# FPGABoard.net
KiCad netlist of a schematic drawn in Altium Designer
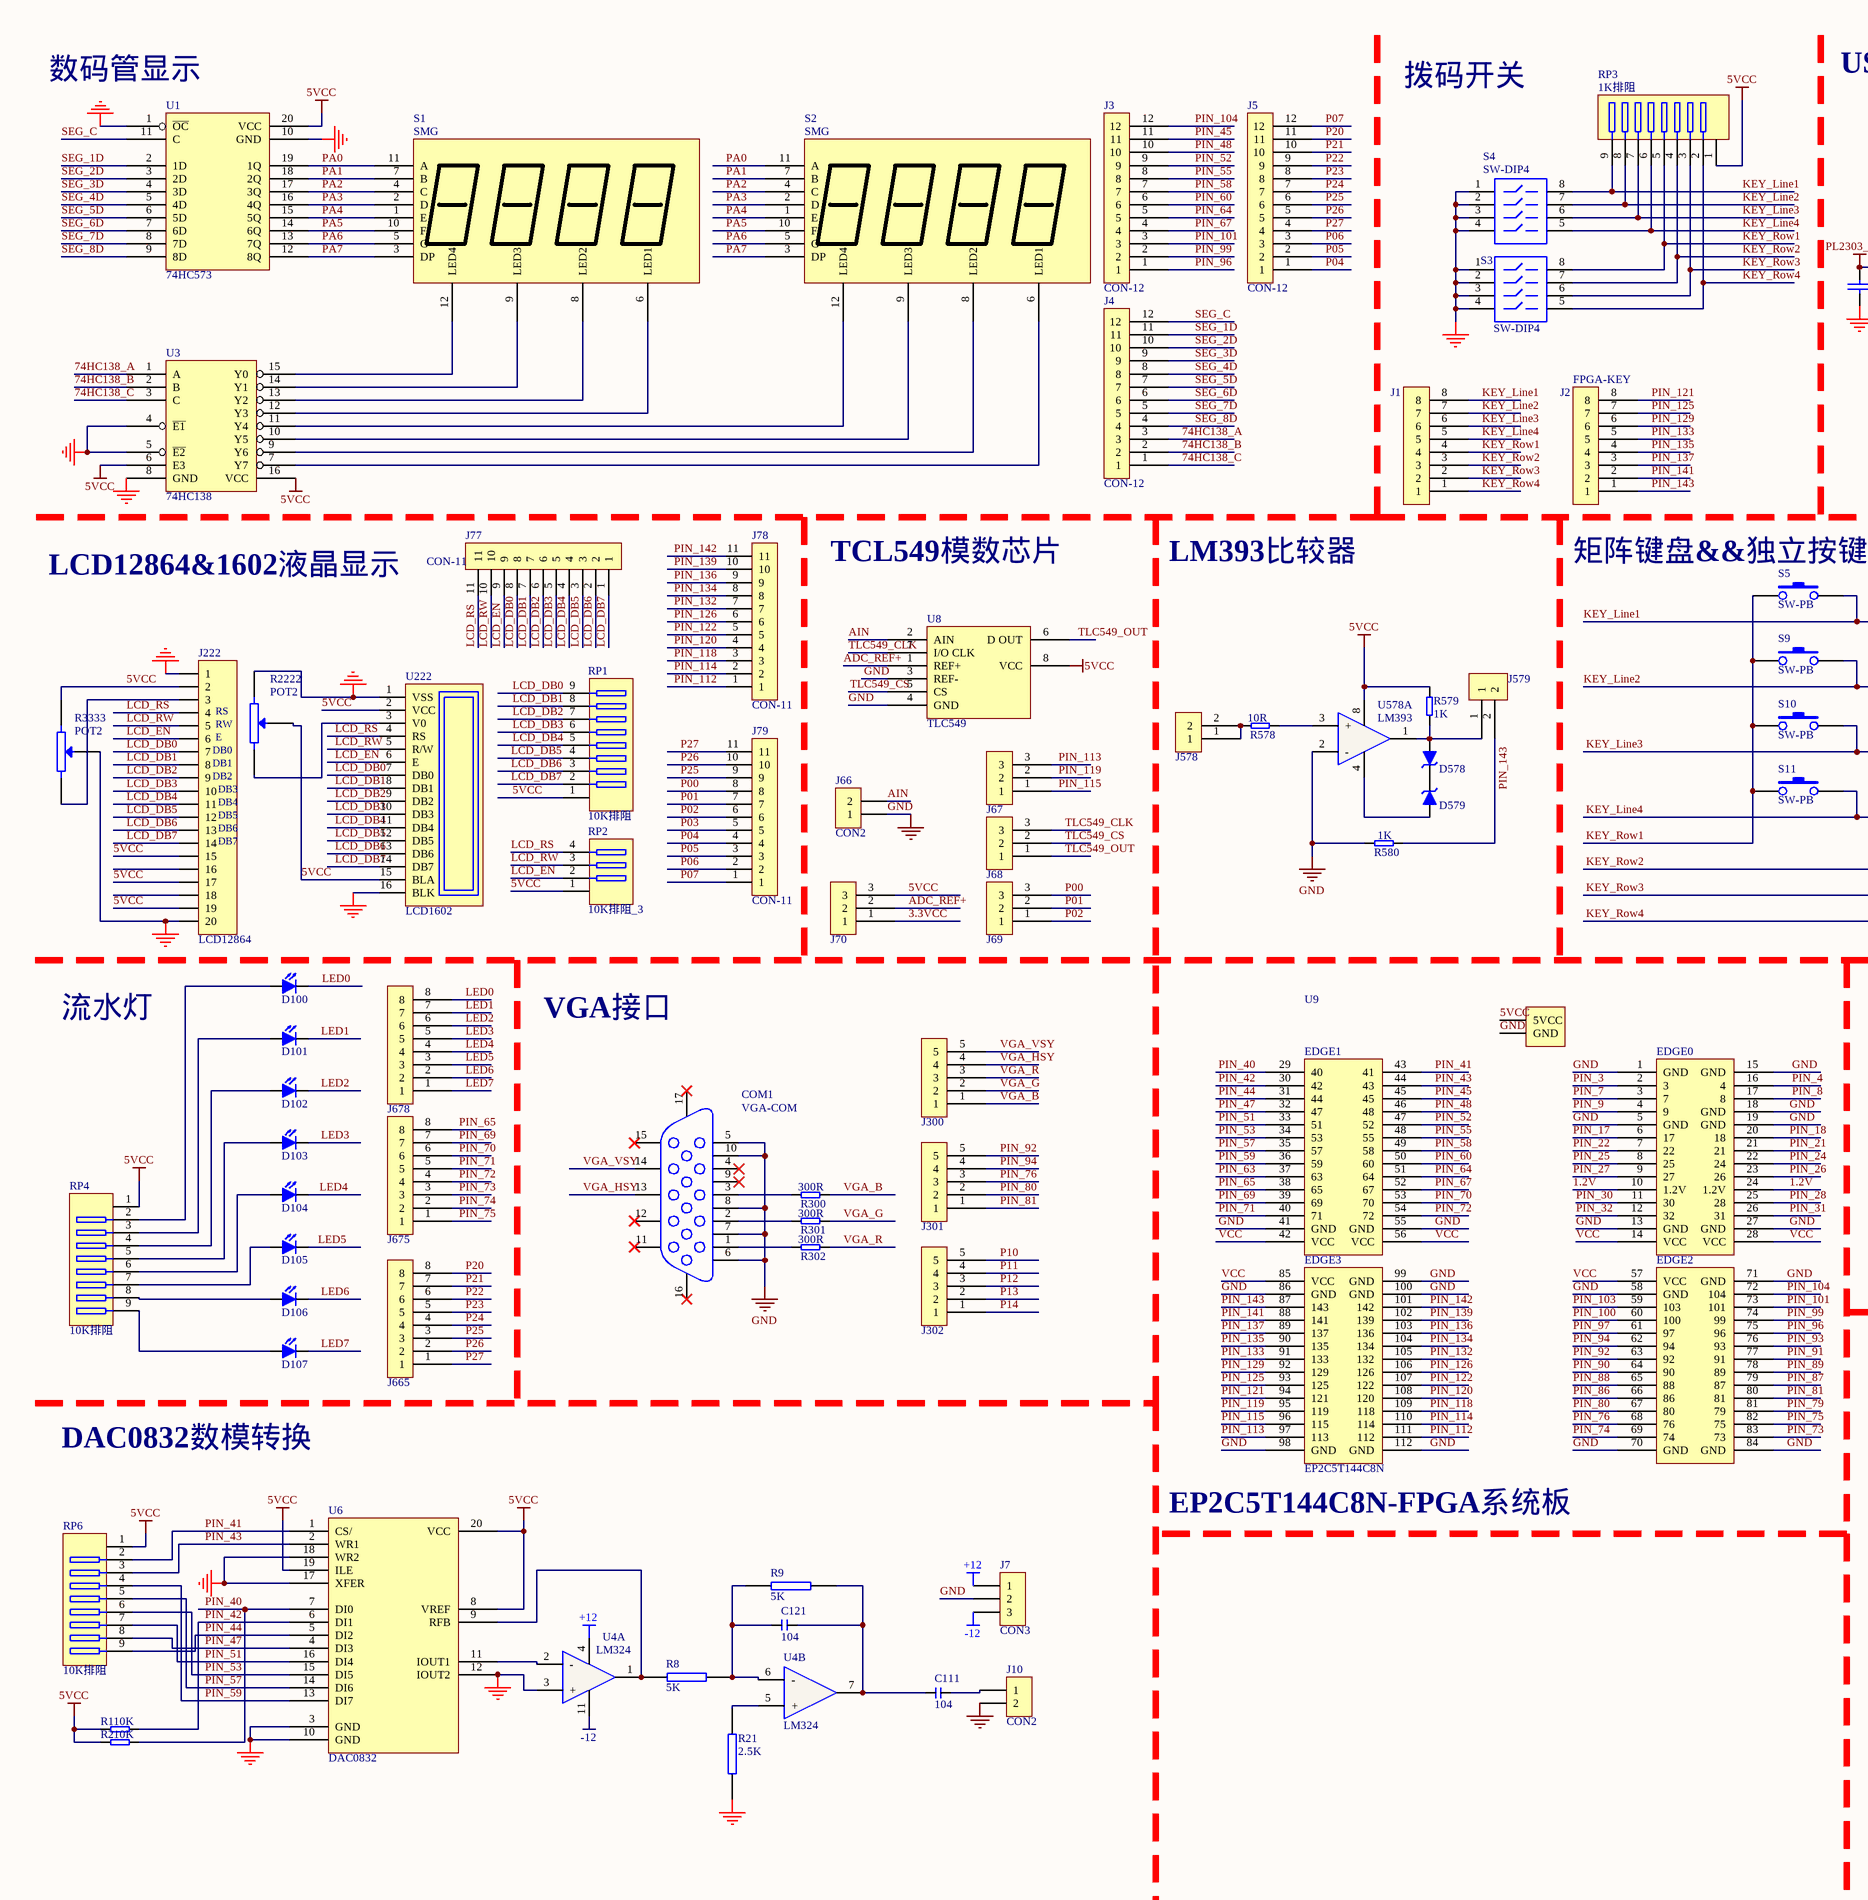
[diagram p0: FPGABoard.SchDoc, left]
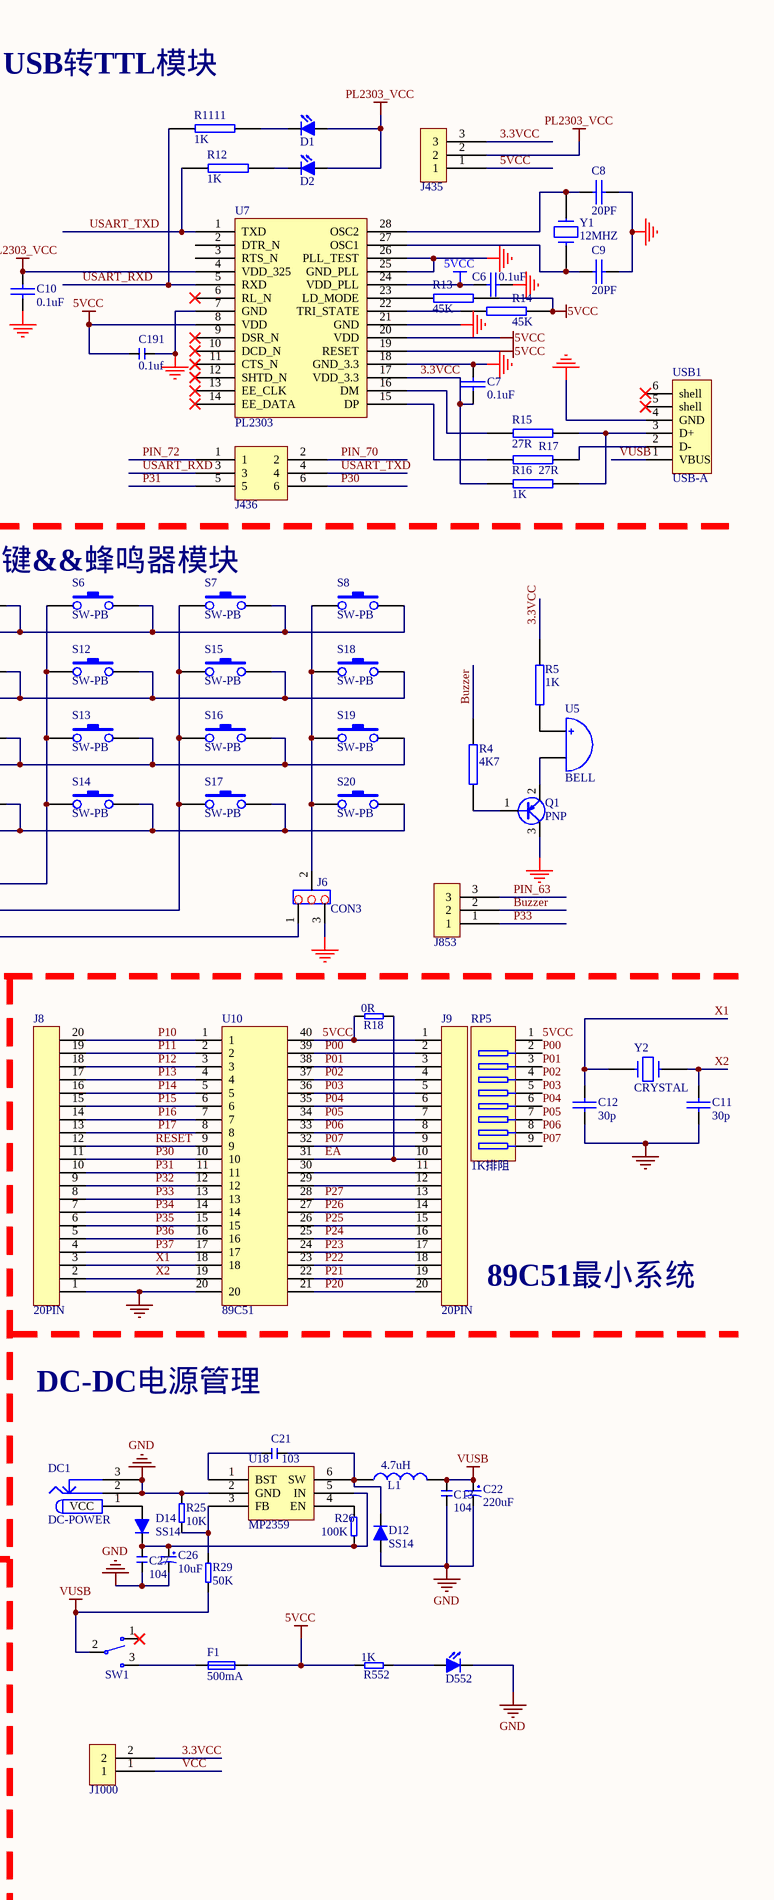
[diagram p1: FPGABoard.SchDoc, right]

(export (version "E")
  (design (tool "Eeschema 10.0.6"))
  (components
    (comp (ref "C6")
      (value "0.1uF")
      (footprint "C0805")
      (description "Capacitor")
      (libsource (lib "*") (part "CAP"))
    )
    (comp (ref "C7")
      (value "0.1uF")
      (footprint "C0805")
      (description "Capacitor")
      (libsource (lib "*") (part "CAP"))
    )
    (comp (ref "C8")
      (value "20PF")
      (footprint "C0805")
      (description "Capacitor")
      (libsource (lib "*") (part "CAP"))
    )
    (comp (ref "C9")
      (value "20PF")
      (footprint "C0805")
      (description "Capacitor")
      (libsource (lib "*") (part "CAP"))
    )
    (comp (ref "C10")
      (value "0.1uF")
      (footprint "C0805")
      (description "Capacitor")
      (libsource (lib "*") (part "CAP"))
    )
    (comp (ref "C11")
      (value "30p")
      (footprint "0805")
      (description "Capacitor")
      (libsource (lib "*") (part "CAP"))
    )
    (comp (ref "C12")
      (value "30p")
      (footprint "0805")
      (description "Capacitor")
      (libsource (lib "*") (part "CAP"))
    )
    (comp (ref "C13") (value "104") (footprint "C0805") (libsource (lib "Allcomments") (part "CAP")))
    (comp (ref "C21") (value "103") (footprint "C0805") (libsource (lib "Allcomments") (part "CAP")))
    (comp (ref "C22")
      (value "220uF")
      (footprint "CA-6.3mmx6.3mm")
      (libsource (lib "Allcomments") (part "CAP-ELEC"))
    )
    (comp (ref "C26")
      (value "10uF")
      (footprint "CA-A-3216L")
      (libsource (lib "Allcomments") (part "CAP-ELEC"))
    )
    (comp (ref "C27") (value "104") (footprint "C0805") (libsource (lib "Allcomments") (part "CAP")))
    (comp (ref "C111") (value "104") (footprint "C0805") (libsource (lib "原理图总库") (part "CAP")))
    (comp (ref "C121") (value "104") (footprint "C0805") (libsource (lib "原理图总库") (part "CAP")))
    (comp (ref "C191") (value "0.1uf") (footprint "C0805") (libsource (lib "Allcomments") (part "CAP")))
    (comp (ref "COM1") (value "VGA-COM") (footprint "VGA-15") (libsource (lib "原理图总库") (part "VGA-COM")))
    (comp (ref "D1") (value "LED") (footprint "LED0805-RED") (libsource (lib "Allcomments") (part "LED")))
    (comp (ref "D2") (value "LED") (footprint "LED0805-RED") (libsource (lib "Allcomments") (part "LED")))
    (comp (ref "D12") (value "SS14") (footprint "DO-214") (libsource (lib "Allcomments") (part "DIODE")))
    (comp (ref "D14") (value "SS14") (footprint "DO-214") (libsource (lib "Allcomments") (part "DIODE")))
    (comp (ref "D100") (value "LED") (footprint "LED0805-RED") (libsource (lib "原理图总库") (part "LED")))
    (comp (ref "D101") (value "LED") (footprint "LED0805-RED") (libsource (lib "原理图总库") (part "LED")))
    (comp (ref "D102") (value "LED") (footprint "LED0805-RED") (libsource (lib "原理图总库") (part "LED")))
    (comp (ref "D103") (value "LED") (footprint "LED0805-RED") (libsource (lib "原理图总库") (part "LED")))
    (comp (ref "D104") (value "LED") (footprint "LED0805-RED") (libsource (lib "原理图总库") (part "LED")))
    (comp (ref "D105") (value "LED") (footprint "LED0805-RED") (libsource (lib "原理图总库") (part "LED")))
    (comp (ref "D106") (value "LED") (footprint "LED0805-RED") (libsource (lib "原理图总库") (part "LED")))
    (comp (ref "D107") (value "LED") (footprint "LED0805-RED") (libsource (lib "原理图总库") (part "LED")))
    (comp (ref "D552") (value "LED") (footprint "LED0805-GREEN") (libsource (lib "原理图总库") (part "LED")))
    (comp (ref "D578")
      (value "DIODE-ZENER3")
      (footprint "D1206")
      (libsource (lib "原理图总库") (part "DIODE-ZENER3"))
    )
    (comp (ref "D579")
      (value "DIODE-ZENER3")
      (footprint "D1206")
      (libsource (lib "原理图总库") (part "DIODE-ZENER3"))
    )
    (comp (ref "DC1") (value "DC-POWER") (footprint "DC-5v") (libsource (lib "Allcomments") (part "DC")))
    (comp (ref "F1") (value "500mA") (footprint "0805") (libsource (lib "Allcomments") (part "FUSE")))
    (comp (ref "J1") (value "CON-8") (footprint "SIP8-2.54") (libsource (lib "Allcomments") (part "CON-8")))
    (comp (ref "J2")
      (value "FPGA-KEY")
      (footprint "SIP8-2.54")
      (libsource (lib "Allcomments") (part "CON-8"))
    )
    (comp (ref "J3")
      (value "CON-12")
      (footprint "SIP12-2.54")
      (libsource (lib "Allcomments") (part "CON-12"))
    )
    (comp (ref "J4")
      (value "CON-12")
      (footprint "SIP12-2.54")
      (libsource (lib "Allcomments") (part "CON-12"))
    )
    (comp (ref "J5")
      (value "CON-12")
      (footprint "SIP12-2.54")
      (libsource (lib "Allcomments") (part "CON-12"))
    )
    (comp (ref "J6") (value "CON3") (footprint "SIP3-2.54") (libsource (lib "") (part "CON3_1")))
    (comp (ref "J7")
      (value "CON3")
      (footprint "SIP3-2.54")
      (description "Connector")
      (libsource (lib "*") (part "CON3"))
    )
    (comp (ref "J8") (value "20PIN") (footprint "SIP20-2.54") (libsource (lib "") (part "20PIN_1")))
    (comp (ref "J9") (value "20PIN") (footprint "SIP20-2.54") (libsource (lib "*") (part "20PIN")))
    (comp (ref "J10")
      (value "CON2")
      (footprint "SIP2-2.54")
      (description "Connector")
      (libsource (lib "") (part "CON2_1"))
    )
    (comp (ref "J66")
      (value "CON2")
      (footprint "SIP2-2.54")
      (description "Connector")
      (libsource (lib "*") (part "CON2"))
    )
    (comp (ref "J67") (value "CON-3") (footprint "SIP3-2.54") (libsource (lib "原理图总库") (part "CON-3")))
    (comp (ref "J68") (value "CON-3") (footprint "SIP3-2.54") (libsource (lib "原理图总库") (part "CON-3")))
    (comp (ref "J69") (value "CON-3") (footprint "SIP3-2.54") (libsource (lib "原理图总库") (part "CON-3")))
    (comp (ref "J70") (value "CON-3") (footprint "SIP3-2.54") (libsource (lib "Allcomments") (part "CON-3")))
    (comp (ref "J77") (value "CON-11") (footprint "SIP11-2.54") (libsource (lib "") (part "CON-11_1")))
    (comp (ref "J78") (value "CON-11") (footprint "SIP11-2.54") (libsource (lib "原理图总库") (part "CON-11")))
    (comp (ref "J79") (value "CON-11") (footprint "SIP11-2.54") (libsource (lib "原理图总库") (part "CON-11")))
    (comp (ref "J222")
      (value "LCD12864")
      (footprint "SIP20-2.54")
      (description "20PIN")
      (libsource (lib "*") (part "LCD12864"))
    )
    (comp (ref "J300") (value "CON-5") (footprint "SIP5-2.54") (libsource (lib "原理图总库") (part "CON-5")))
    (comp (ref "J301") (value "CON-5") (footprint "SIP5-2.54") (libsource (lib "原理图总库") (part "CON-5")))
    (comp (ref "J302") (value "CON-5") (footprint "SIP5-2.54") (libsource (lib "原理图总库") (part "CON-5")))
    (comp (ref "J435") (value "CON-3") (footprint "SIP3-2.54") (libsource (lib "Allcomments") (part "CON-3")))
    (comp (ref "J436")
      (value "CON-2*3")
      (footprint "J2X3-2.54mm")
      (libsource (lib "Allcomments") (part "CON-2*3"))
    )
    (comp (ref "J578") (value "CON-2") (footprint "J1x2-2.54mm") (libsource (lib "") (part "CON-2_1")))
    (comp (ref "J579") (value "CON-2") (footprint "J1x2-2.54mm") (libsource (lib "原理图总库") (part "CON-2")))
    (comp (ref "J665") (value "CON-8") (footprint "SIP8-2.54") (libsource (lib "原理图总库") (part "CON-8")))
    (comp (ref "J675") (value "CON-8") (footprint "SIP8-2.54") (libsource (lib "原理图总库") (part "CON-8")))
    (comp (ref "J678") (value "CON-8") (footprint "SIP8-2.54") (libsource (lib "原理图总库") (part "CON-8")))
    (comp (ref "J853") (value "CON-3") (footprint "SIP3-2.54") (libsource (lib "原理图总库") (part "CON-3")))
    (comp (ref "J1000") (value "CON-2") (footprint "J1x2-2.54mm") (libsource (lib "") (part "CON-2_1")))
    (comp (ref "L1") (value "4.7uH") (footprint "L-SOP74") (libsource (lib "Allcomments") (part "INDUCTOR")))
    (comp (ref "Q1") (value "PNP") (footprint "SOT-23A") (libsource (lib "原理图总库") (part "AUDION-PNP")))
    (comp (ref "R1") (value "10K") (footprint "R-0805") (libsource (lib "Allcomments") (part "RES")))
    (comp (ref "R2") (value "10K") (footprint "R-0805") (libsource (lib "Allcomments") (part "RES")))
    (comp (ref "R4") (value "4K7") (footprint "R0805") (libsource (lib "*") (part "RES2")))
    (comp (ref "R5") (value "1K") (footprint "R0805") (libsource (lib "*") (part "RES2")))
    (comp (ref "R8") (value "5K") (footprint "R0805") (libsource (lib "*") (part "RES2")))
    (comp (ref "R9") (value "5K") (footprint "R0805") (libsource (lib "*") (part "RES2")))
    (comp (ref "R12") (value "1K") (footprint "0805") (libsource (lib "*") (part "RES2")))
    (comp (ref "R13") (value "45K") (footprint "0805") (libsource (lib "*") (part "RES2")))
    (comp (ref "R14") (value "45K") (footprint "0805") (libsource (lib "*") (part "RES2")))
    (comp (ref "R15") (value "27R") (footprint "0805") (libsource (lib "*") (part "RES2")))
    (comp (ref "R16") (value "1K") (footprint "0805") (libsource (lib "*") (part "RES2")))
    (comp (ref "R17") (value "27R") (footprint "0805") (libsource (lib "*") (part "RES2")))
    (comp (ref "R18") (value "0R") (footprint "R0805") (libsource (lib "Allcomments") (part "RES")))
    (comp (ref "R21") (value "2.5K") (footprint "R0805") (libsource (lib "*") (part "RES2")))
    (comp (ref "R25") (value "10K") (footprint "R-0805") (libsource (lib "Allcomments") (part "RES")))
    (comp (ref "R26") (value "100K") (footprint "R-0805") (libsource (lib "Allcomments") (part "RES")))
    (comp (ref "R29") (value "50K") (footprint "R-0805") (libsource (lib "Allcomments") (part "RES")))
    (comp (ref "R300") (value "300R") (footprint "R-0805") (libsource (lib "原理图总库") (part "RES")))
    (comp (ref "R301") (value "300R") (footprint "R-0805") (libsource (lib "原理图总库") (part "RES")))
    (comp (ref "R302") (value "300R") (footprint "R-0805") (libsource (lib "原理图总库") (part "RES")))
    (comp (ref "R552") (value "1K") (footprint "0805") (libsource (lib "原理图总库") (part "RES")))
    (comp (ref "R578") (value "10R") (footprint "R-0805") (libsource (lib "原理图总库") (part "RES")))
    (comp (ref "R579") (value "1K") (footprint "R-0805") (libsource (lib "原理图总库") (part "RES")))
    (comp (ref "R580") (value "1K") (footprint "R-0805") (libsource (lib "原理图总库") (part "RES")))
    (comp (ref "R1111") (value "1K") (footprint "0805") (libsource (lib "*") (part "RES2")))
    (comp (ref "R2222")
      (value "POT2")
      (footprint "VR5")
      (description "Potentiometer")
      (libsource (lib "*") (part "POT2"))
    )
    (comp (ref "R3333")
      (value "POT2")
      (footprint "VR5")
      (description "Potentiometer")
      (libsource (lib "*") (part "POT2"))
    )
    (comp (ref "RP1")
      (value "10K排阻")
      (footprint "SIP9-2.54")
      (description "330")
      (libsource (lib "") (part "10K排阻_2"))
    )
    (comp (ref "RP2")
      (value "10K排阻_3")
      (footprint "SIP4-2.54")
      (description "330")
      (libsource (lib "*") (part "10K排阻_3"))
    )
    (comp (ref "RP3")
      (value "1K排阻")
      (footprint "SIP9-2.54")
      (description "330")
      (libsource (lib "") (part "10K排阻_1"))
    )
    (comp (ref "RP4")
      (value "10K排阻")
      (footprint "SIP9-2.54")
      (description "330")
      (libsource (lib "*") (part "10K排阻"))
    )
    (comp (ref "RP5")
      (value "1K排阻")
      (footprint "SIP9-2.54")
      (description "330")
      (libsource (lib "*") (part "10K排阻"))
    )
    (comp (ref "RP6")
      (value "10K排阻")
      (footprint "SIP9-2.54")
      (description "330")
      (libsource (lib "*") (part "10K排阻"))
    )
    (comp (ref "S1") (value "SMG") (footprint "LED4_0.28_DIP12") (libsource (lib "*") (part "SMG")))
    (comp (ref "S2") (value "SMG") (footprint "LED4_0.28_DIP12") (libsource (lib "*") (part "SMG")))
    (comp (ref "S3") (value "SW-DIP4") (footprint "DIP-KEY-4") (libsource (lib "*") (part "SW-DIP4")))
    (comp (ref "S4") (value "SW-DIP4") (footprint "DIP-KEY-4") (libsource (lib "*") (part "SW-DIP4")))
    (comp (ref "S5") (value "SW-PB") (footprint "KEY") (libsource (lib "*") (part "SW-PB")))
    (comp (ref "S6") (value "SW-PB") (footprint "KEY") (libsource (lib "*") (part "SW-PB")))
    (comp (ref "S7") (value "SW-PB") (footprint "KEY") (libsource (lib "*") (part "SW-PB")))
    (comp (ref "S8") (value "SW-PB") (footprint "KEY") (libsource (lib "*") (part "SW-PB")))
    (comp (ref "S9") (value "SW-PB") (footprint "KEY") (libsource (lib "*") (part "SW-PB")))
    (comp (ref "S10") (value "SW-PB") (footprint "KEY") (libsource (lib "*") (part "SW-PB")))
    (comp (ref "S11") (value "SW-PB") (footprint "KEY") (libsource (lib "*") (part "SW-PB")))
    (comp (ref "S12") (value "SW-PB") (footprint "KEY") (libsource (lib "*") (part "SW-PB")))
    (comp (ref "S13") (value "SW-PB") (footprint "KEY") (libsource (lib "*") (part "SW-PB")))
    (comp (ref "S14") (value "SW-PB") (footprint "KEY") (libsource (lib "*") (part "SW-PB")))
    (comp (ref "S15") (value "SW-PB") (footprint "KEY") (libsource (lib "*") (part "SW-PB")))
    (comp (ref "S16") (value "SW-PB") (footprint "KEY") (libsource (lib "*") (part "SW-PB")))
    (comp (ref "S17") (value "SW-PB") (footprint "KEY") (libsource (lib "*") (part "SW-PB")))
    (comp (ref "S18") (value "SW-PB") (footprint "KEY") (libsource (lib "*") (part "SW-PB")))
    (comp (ref "S19") (value "SW-PB") (footprint "KEY") (libsource (lib "*") (part "SW-PB")))
    (comp (ref "S20") (value "SW-PB") (footprint "KEY") (libsource (lib "*") (part "SW-PB")))
    (comp (ref "SW1")
      (value "SW-SPDP")
      (footprint "SW-DPDT")
      (libsource (lib "Allcomments") (part "SW-SPDP"))
    )
    (comp (ref "U1") (value "74HC573") (footprint "SO-20W") (libsource (lib "*") (part "74HC573")))
    (comp (ref "U3") (value "74HC138") (footprint "SOP-16-NB") (libsource (lib "*") (part "74HC138")))
    (comp (ref "U4") (value "LM324") (footprint "SOP14-225-50") (libsource (lib "原理图总库") (part "LM324")))
    (comp (ref "U5")
      (value "BELL")
      (footprint "BELL")
      (description "Bell")
      (libsource (lib "*") (part "BELL"))
    )
    (comp (ref "U6") (value "DAC0832") (footprint "DIP-20N") (libsource (lib "*") (part "DAC0832")))
    (comp (ref "U7") (value "PL2303") (footprint "SSOP-SS28_N") (libsource (lib "*") (part "PL2303")))
    (comp (ref "U8") (value "TLC549") (footprint "SOP-8-NB") (libsource (lib "*") (part "TLC549")))
    (comp (ref "U9") (value "EP2C5T144C8N") (footprint "HXB") (libsource (lib "*") (part "EP2C5T144C8N")))
    (comp (ref "U10") (value "89C51") (footprint "ZIP_40") (libsource (lib "*") (part "89C51")))
    (comp (ref "U18") (value "MP2359") (footprint "SOT23-6") (libsource (lib "Allcomments") (part "MP2359")))
    (comp (ref "U222")
      (value "LCD1602")
      (footprint "SIP16-2.54")
      (description "16PIN")
      (libsource (lib "*") (part "LCD1602"))
    )
    (comp (ref "U578") (value "LM393") (footprint "SOP-8-NB") (libsource (lib "原理图总库") (part "LM393")))
    (comp (ref "USB1")
      (value "USB-A")
      (footprint "USB-HD-1X1-1")
      (libsource (lib "Allcomments") (part "USB-A"))
    )
    (comp (ref "Y1")
      (value "12MHZ")
      (footprint "XTAL")
      (description "Crystal")
      (libsource (lib "*") (part "CRYSTAL"))
    )
    (comp (ref "Y2")
      (value "CRYSTAL")
      (footprint "XTAL2")
      (description "Crystal")
      (libsource (lib "*") (part "CRYSTAL"))
    )
  )
  (nets
    (net (code "1") (name "+12") (class "Default")
      (node (ref "J7") (pin "1") (pinfunction "1_1") (pintype "passive"))
      (node (ref "U4") (pin "4") (pinfunction "4_4") (pintype "passive"))
    )
    (net (code "2") (name "-12") (class "Default")
      (node (ref "J7") (pin "3") (pinfunction "3_3") (pintype "passive"))
      (node (ref "U4") (pin "11") (pinfunction "11_11") (pintype "passive"))
    )
    (net (code "3") (name "/1.2V") (class "Default")
      (node (ref "U9") (pin "10") (pinfunction "1.2V_10") (pintype "passive"))
      (node (ref "U9") (pin "24") (pinfunction "1.2V_24") (pintype "passive"))
    )
    (net (code "4") (name "/3.3VCC") (class "Default")
      (node (ref "C7") (pin "2") (pinfunction "2_2") (pintype "passive"))
      (node (ref "J1000") (pin "2") (pinfunction "2_2") (pintype "passive"))
      (node (ref "J435") (pin "3") (pinfunction "3_3") (pintype "passive"))
      (node (ref "J70") (pin "1") (pinfunction "1_1") (pintype "passive"))
      (node (ref "R16") (pin "2") (pinfunction "2_2") (pintype "passive"))
      (node (ref "R5") (pin "2") (pinfunction "2_2") (pintype "passive"))
      (node (ref "U7") (pin "17") (pinfunction "VDD_3.3_17") (pintype "passive"))
    )
    (net (code "5") (name "/74HC138_A") (class "Default")
      (node (ref "J4") (pin "3") (pinfunction "3_3") (pintype "passive"))
      (node (ref "U3") (pin "1") (pinfunction "A_1") (pintype "passive"))
    )
    (net (code "6") (name "/74HC138_B") (class "Default")
      (node (ref "J4") (pin "2") (pinfunction "2_2") (pintype "passive"))
      (node (ref "U3") (pin "2") (pinfunction "B_2") (pintype "passive"))
    )
    (net (code "7") (name "/74HC138_C") (class "Default")
      (node (ref "J4") (pin "1") (pinfunction "1_1") (pintype "passive"))
      (node (ref "U3") (pin "3") (pinfunction "C_3") (pintype "passive"))
    )
    (net (code "8") (name "/ADC_REF+") (class "Default")
      (node (ref "J70") (pin "2") (pinfunction "2_2") (pintype "passive"))
      (node (ref "U8") (pin "1") (pinfunction "REF+_1") (pintype "passive"))
    )
    (net (code "9") (name "/AIN") (class "Default")
      (node (ref "J66") (pin "2") (pinfunction "2_2") (pintype "passive"))
      (node (ref "U8") (pin "2") (pinfunction "AIN_2") (pintype "passive"))
    )
    (net (code "10") (name "/Buzzer") (class "Default")
      (node (ref "J853") (pin "2") (pinfunction "2_2") (pintype "passive"))
      (node (ref "R4") (pin "1") (pinfunction "1_1") (pintype "passive"))
    )
    (net (code "11") (name "/EA") (class "Default")
      (node (ref "J9") (pin "10") (pinfunction "10_10") (pintype "passive"))
      (node (ref "R18") (pin "2") (pinfunction "2_2") (pintype "passive"))
      (node (ref "U10") (pin "31") (pinfunction "31_31") (pintype "passive"))
    )
    (net (code "12") (name "/KEY_Line1") (class "Default")
      (node (ref "J1") (pin "8") (pinfunction "8_8") (pintype "passive"))
      (node (ref "RP3") (pin "9") (pinfunction "9_9") (pintype "passive"))
      (node (ref "S4") (pin "8") (pinfunction "8_8") (pintype "passive"))
      (node (ref "S5") (pin "3") (pinfunction "3_3") (pintype "passive"))
      (node (ref "S6") (pin "3") (pinfunction "3_3") (pintype "passive"))
      (node (ref "S7") (pin "3") (pinfunction "3_3") (pintype "passive"))
      (node (ref "S8") (pin "3") (pinfunction "3_3") (pintype "passive"))
    )
    (net (code "13") (name "/KEY_Line2") (class "Default")
      (node (ref "J1") (pin "7") (pinfunction "7_7") (pintype "passive"))
      (node (ref "RP3") (pin "8") (pinfunction "8_8") (pintype "passive"))
      (node (ref "S12") (pin "3") (pinfunction "3_3") (pintype "passive"))
      (node (ref "S15") (pin "3") (pinfunction "3_3") (pintype "passive"))
      (node (ref "S18") (pin "3") (pinfunction "3_3") (pintype "passive"))
      (node (ref "S4") (pin "7") (pinfunction "7_7") (pintype "passive"))
      (node (ref "S9") (pin "3") (pinfunction "3_3") (pintype "passive"))
    )
    (net (code "14") (name "/KEY_Line3") (class "Default")
      (node (ref "J1") (pin "6") (pinfunction "6_6") (pintype "passive"))
      (node (ref "RP3") (pin "7") (pinfunction "7_7") (pintype "passive"))
      (node (ref "S10") (pin "3") (pinfunction "3_3") (pintype "passive"))
      (node (ref "S13") (pin "3") (pinfunction "3_3") (pintype "passive"))
      (node (ref "S16") (pin "3") (pinfunction "3_3") (pintype "passive"))
      (node (ref "S19") (pin "3") (pinfunction "3_3") (pintype "passive"))
      (node (ref "S4") (pin "6") (pinfunction "6_6") (pintype "passive"))
    )
    (net (code "15") (name "/KEY_Line4") (class "Default")
      (node (ref "J1") (pin "5") (pinfunction "5_5") (pintype "passive"))
      (node (ref "RP3") (pin "6") (pinfunction "6_6") (pintype "passive"))
      (node (ref "S11") (pin "3") (pinfunction "3_3") (pintype "passive"))
      (node (ref "S14") (pin "3") (pinfunction "3_3") (pintype "passive"))
      (node (ref "S17") (pin "3") (pinfunction "3_3") (pintype "passive"))
      (node (ref "S20") (pin "3") (pinfunction "3_3") (pintype "passive"))
      (node (ref "S4") (pin "5") (pinfunction "5_5") (pintype "passive"))
    )
    (net (code "16") (name "/KEY_Row1") (class "Default")
      (node (ref "J1") (pin "4") (pinfunction "4_4") (pintype "passive"))
      (node (ref "RP3") (pin "5") (pinfunction "5_5") (pintype "passive"))
      (node (ref "S10") (pin "1") (pinfunction "1_1") (pintype "passive"))
      (node (ref "S11") (pin "1") (pinfunction "1_1") (pintype "passive"))
      (node (ref "S3") (pin "8") (pinfunction "8_8") (pintype "passive"))
      (node (ref "S5") (pin "1") (pinfunction "1_1") (pintype "passive"))
      (node (ref "S9") (pin "1") (pinfunction "1_1") (pintype "passive"))
    )
    (net (code "17") (name "/KEY_Row2") (class "Default")
      (node (ref "J1") (pin "3") (pinfunction "3_3") (pintype "passive"))
      (node (ref "RP3") (pin "4") (pinfunction "4_4") (pintype "passive"))
      (node (ref "S12") (pin "1") (pinfunction "1_1") (pintype "passive"))
      (node (ref "S13") (pin "1") (pinfunction "1_1") (pintype "passive"))
      (node (ref "S14") (pin "1") (pinfunction "1_1") (pintype "passive"))
      (node (ref "S3") (pin "7") (pinfunction "7_7") (pintype "passive"))
      (node (ref "S6") (pin "1") (pinfunction "1_1") (pintype "passive"))
    )
    (net (code "18") (name "/KEY_Row3") (class "Default")
      (node (ref "J1") (pin "2") (pinfunction "2_2") (pintype "passive"))
      (node (ref "RP3") (pin "3") (pinfunction "3_3") (pintype "passive"))
      (node (ref "S15") (pin "1") (pinfunction "1_1") (pintype "passive"))
      (node (ref "S16") (pin "1") (pinfunction "1_1") (pintype "passive"))
      (node (ref "S17") (pin "1") (pinfunction "1_1") (pintype "passive"))
      (node (ref "S3") (pin "6") (pinfunction "6_6") (pintype "passive"))
      (node (ref "S7") (pin "1") (pinfunction "1_1") (pintype "passive"))
    )
    (net (code "19") (name "/KEY_Row4") (class "Default")
      (node (ref "J1") (pin "1") (pinfunction "1_1") (pintype "passive"))
      (node (ref "J6") (pin "1") (pinfunction "1_1") (pintype "passive"))
      (node (ref "RP3") (pin "2") (pinfunction "2_2") (pintype "passive"))
      (node (ref "S3") (pin "5") (pinfunction "5_5") (pintype "passive"))
    )
    (net (code "20") (name "/LCD_DB0") (class "Default")
      (node (ref "J222") (pin "7") (pinfunction "7_7") (pintype "passive"))
      (node (ref "J77") (pin "8") (pinfunction "8_8") (pintype "passive"))
      (node (ref "RP1") (pin "9") (pinfunction "9_9") (pintype "passive"))
      (node (ref "U222") (pin "7") (pinfunction "DB0_7") (pintype "passive"))
    )
    (net (code "21") (name "/LCD_DB1") (class "Default")
      (node (ref "J222") (pin "8") (pinfunction "8_8") (pintype "passive"))
      (node (ref "J77") (pin "7") (pinfunction "7_7") (pintype "passive"))
      (node (ref "RP1") (pin "8") (pinfunction "8_8") (pintype "passive"))
      (node (ref "U222") (pin "8") (pinfunction "DB1_8") (pintype "passive"))
    )
    (net (code "22") (name "/LCD_DB2") (class "Default")
      (node (ref "J222") (pin "9") (pinfunction "9_9") (pintype "passive"))
      (node (ref "J77") (pin "6") (pinfunction "6_6") (pintype "passive"))
      (node (ref "RP1") (pin "7") (pinfunction "7_7") (pintype "passive"))
      (node (ref "U222") (pin "9") (pinfunction "DB2_9") (pintype "passive"))
    )
    (net (code "23") (name "/LCD_DB3") (class "Default")
      (node (ref "J222") (pin "10") (pinfunction "10_10") (pintype "passive"))
      (node (ref "J77") (pin "5") (pinfunction "5_5") (pintype "passive"))
      (node (ref "RP1") (pin "6") (pinfunction "6_6") (pintype "passive"))
      (node (ref "U222") (pin "10") (pinfunction "DB3_10") (pintype "passive"))
    )
    (net (code "24") (name "/LCD_DB4") (class "Default")
      (node (ref "J222") (pin "11") (pinfunction "11_11") (pintype "passive"))
      (node (ref "J77") (pin "4") (pinfunction "4_4") (pintype "passive"))
      (node (ref "RP1") (pin "5") (pinfunction "5_5") (pintype "passive"))
      (node (ref "U222") (pin "11") (pinfunction "DB4_11") (pintype "passive"))
    )
    (net (code "25") (name "/LCD_DB5") (class "Default")
      (node (ref "J222") (pin "12") (pinfunction "12_12") (pintype "passive"))
      (node (ref "J77") (pin "3") (pinfunction "3_3") (pintype "passive"))
      (node (ref "RP1") (pin "4") (pinfunction "4_4") (pintype "passive"))
      (node (ref "U222") (pin "12") (pinfunction "DB5_12") (pintype "passive"))
    )
    (net (code "26") (name "/LCD_DB6") (class "Default")
      (node (ref "J222") (pin "13") (pinfunction "13_13") (pintype "passive"))
      (node (ref "J77") (pin "2") (pinfunction "2_2") (pintype "passive"))
      (node (ref "RP1") (pin "3") (pinfunction "3_3") (pintype "passive"))
      (node (ref "U222") (pin "13") (pinfunction "DB6_13") (pintype "passive"))
    )
    (net (code "27") (name "/LCD_DB7") (class "Default")
      (node (ref "J222") (pin "14") (pinfunction "14_14") (pintype "passive"))
      (node (ref "J77") (pin "1") (pinfunction "1_1") (pintype "passive"))
      (node (ref "RP1") (pin "2") (pinfunction "2_2") (pintype "passive"))
      (node (ref "U222") (pin "14") (pinfunction "DB7_14") (pintype "passive"))
    )
    (net (code "28") (name "/LCD_EN") (class "Default")
      (node (ref "J222") (pin "6") (pinfunction "6_6") (pintype "passive"))
      (node (ref "J77") (pin "9") (pinfunction "9_9") (pintype "passive"))
      (node (ref "RP2") (pin "2") (pinfunction "2_2") (pintype "passive"))
      (node (ref "U222") (pin "6") (pinfunction "E_6") (pintype "passive"))
    )
    (net (code "29") (name "/LCD_RS") (class "Default")
      (node (ref "J222") (pin "4") (pinfunction "4_4") (pintype "passive"))
      (node (ref "J77") (pin "11") (pinfunction "11_11") (pintype "passive"))
      (node (ref "RP2") (pin "4") (pinfunction "4_4") (pintype "passive"))
      (node (ref "U222") (pin "4") (pinfunction "RS_4") (pintype "passive"))
    )
    (net (code "30") (name "/LCD_RW") (class "Default")
      (node (ref "J222") (pin "5") (pinfunction "5_5") (pintype "passive"))
      (node (ref "J77") (pin "10") (pinfunction "10_10") (pintype "passive"))
      (node (ref "RP2") (pin "3") (pinfunction "3_3") (pintype "passive"))
      (node (ref "U222") (pin "5") (pinfunction "R/W_5") (pintype "passive"))
    )
    (net (code "31") (name "/LED0") (class "Default")
      (node (ref "D100") (pin "2") (pinfunction "2_2") (pintype "passive"))
      (node (ref "J678") (pin "8") (pinfunction "8_8") (pintype "passive"))
    )
    (net (code "32") (name "/LED1") (class "Default")
      (node (ref "D101") (pin "2") (pinfunction "2_2") (pintype "passive"))
      (node (ref "J678") (pin "7") (pinfunction "7_7") (pintype "passive"))
    )
    (net (code "33") (name "/LED2") (class "Default")
      (node (ref "D102") (pin "2") (pinfunction "2_2") (pintype "passive"))
      (node (ref "J678") (pin "6") (pinfunction "6_6") (pintype "passive"))
    )
    (net (code "34") (name "/LED3") (class "Default")
      (node (ref "D103") (pin "2") (pinfunction "2_2") (pintype "passive"))
      (node (ref "J678") (pin "5") (pinfunction "5_5") (pintype "passive"))
    )
    (net (code "35") (name "/LED4") (class "Default")
      (node (ref "D104") (pin "2") (pinfunction "2_2") (pintype "passive"))
      (node (ref "J678") (pin "4") (pinfunction "4_4") (pintype "passive"))
    )
    (net (code "36") (name "/LED5") (class "Default")
      (node (ref "D105") (pin "2") (pinfunction "2_2") (pintype "passive"))
      (node (ref "J678") (pin "3") (pinfunction "3_3") (pintype "passive"))
    )
    (net (code "37") (name "/LED6") (class "Default")
      (node (ref "D106") (pin "2") (pinfunction "2_2") (pintype "passive"))
      (node (ref "J678") (pin "2") (pinfunction "2_2") (pintype "passive"))
    )
    (net (code "38") (name "/LED7") (class "Default")
      (node (ref "D107") (pin "2") (pinfunction "2_2") (pintype "passive"))
      (node (ref "J678") (pin "1") (pinfunction "1_1") (pintype "passive"))
    )
    (net (code "39") (name "/P00") (class "Default")
      (node (ref "J69") (pin "3") (pinfunction "3_3") (pintype "passive"))
      (node (ref "J79") (pin "8") (pinfunction "8_8") (pintype "passive"))
      (node (ref "J9") (pin "2") (pinfunction "2_2") (pintype "passive"))
      (node (ref "RP5") (pin "2") (pinfunction "2_2") (pintype "passive"))
      (node (ref "U10") (pin "39") (pinfunction "39_39") (pintype "passive"))
    )
    (net (code "40") (name "/P01") (class "Default")
      (node (ref "J69") (pin "2") (pinfunction "2_2") (pintype "passive"))
      (node (ref "J79") (pin "7") (pinfunction "7_7") (pintype "passive"))
      (node (ref "J9") (pin "3") (pinfunction "3_3") (pintype "passive"))
      (node (ref "RP5") (pin "3") (pinfunction "3_3") (pintype "passive"))
      (node (ref "U10") (pin "38") (pinfunction "38_38") (pintype "passive"))
    )
    (net (code "41") (name "/P02") (class "Default")
      (node (ref "J69") (pin "1") (pinfunction "1_1") (pintype "passive"))
      (node (ref "J79") (pin "6") (pinfunction "6_6") (pintype "passive"))
      (node (ref "J9") (pin "4") (pinfunction "4_4") (pintype "passive"))
      (node (ref "RP5") (pin "4") (pinfunction "4_4") (pintype "passive"))
      (node (ref "U10") (pin "37") (pinfunction "37_37") (pintype "passive"))
    )
    (net (code "42") (name "/P03") (class "Default")
      (node (ref "J79") (pin "5") (pinfunction "5_5") (pintype "passive"))
      (node (ref "J9") (pin "5") (pinfunction "5_5") (pintype "passive"))
      (node (ref "RP5") (pin "5") (pinfunction "5_5") (pintype "passive"))
      (node (ref "U10") (pin "36") (pinfunction "36_36") (pintype "passive"))
    )
    (net (code "43") (name "/P04") (class "Default")
      (node (ref "J5") (pin "1") (pinfunction "1_1") (pintype "passive"))
      (node (ref "J79") (pin "4") (pinfunction "4_4") (pintype "passive"))
      (node (ref "J9") (pin "6") (pinfunction "6_6") (pintype "passive"))
      (node (ref "RP5") (pin "6") (pinfunction "6_6") (pintype "passive"))
      (node (ref "U10") (pin "35") (pinfunction "35_35") (pintype "passive"))
    )
    (net (code "44") (name "/P05") (class "Default")
      (node (ref "J5") (pin "2") (pinfunction "2_2") (pintype "passive"))
      (node (ref "J79") (pin "3") (pinfunction "3_3") (pintype "passive"))
      (node (ref "J9") (pin "7") (pinfunction "7_7") (pintype "passive"))
      (node (ref "RP5") (pin "7") (pinfunction "7_7") (pintype "passive"))
      (node (ref "U10") (pin "34") (pinfunction "34_34") (pintype "passive"))
    )
    (net (code "45") (name "/P06") (class "Default")
      (node (ref "J5") (pin "3") (pinfunction "3_3") (pintype "passive"))
      (node (ref "J79") (pin "2") (pinfunction "2_2") (pintype "passive"))
      (node (ref "J9") (pin "8") (pinfunction "8_8") (pintype "passive"))
      (node (ref "RP5") (pin "8") (pinfunction "8_8") (pintype "passive"))
      (node (ref "U10") (pin "33") (pinfunction "33_33") (pintype "passive"))
    )
    (net (code "46") (name "/P07") (class "Default")
      (node (ref "J5") (pin "12") (pinfunction "12_12") (pintype "passive"))
      (node (ref "J79") (pin "1") (pinfunction "1_1") (pintype "passive"))
      (node (ref "J9") (pin "9") (pinfunction "9_9") (pintype "passive"))
      (node (ref "RP5") (pin "9") (pinfunction "9_9") (pintype "passive"))
      (node (ref "U10") (pin "32") (pinfunction "32_32") (pintype "passive"))
    )
    (net (code "47") (name "/P10") (class "Default")
      (node (ref "J302") (pin "5") (pinfunction "5_5") (pintype "passive"))
      (node (ref "J8") (pin "20") (pinfunction "20_20") (pintype "passive"))
      (node (ref "U10") (pin "1") (pinfunction "1_1") (pintype "passive"))
    )
    (net (code "48") (name "/P11") (class "Default")
      (node (ref "J302") (pin "4") (pinfunction "4_4") (pintype "passive"))
      (node (ref "J8") (pin "19") (pinfunction "19_19") (pintype "passive"))
      (node (ref "U10") (pin "2") (pinfunction "2_2") (pintype "passive"))
    )
    (net (code "49") (name "/P12") (class "Default")
      (node (ref "J302") (pin "3") (pinfunction "3_3") (pintype "passive"))
      (node (ref "J8") (pin "18") (pinfunction "18_18") (pintype "passive"))
      (node (ref "U10") (pin "3") (pinfunction "3_3") (pintype "passive"))
    )
    (net (code "50") (name "/P13") (class "Default")
      (node (ref "J302") (pin "2") (pinfunction "2_2") (pintype "passive"))
      (node (ref "J8") (pin "17") (pinfunction "17_17") (pintype "passive"))
      (node (ref "U10") (pin "4") (pinfunction "4_4") (pintype "passive"))
    )
    (net (code "51") (name "/P14") (class "Default")
      (node (ref "J302") (pin "1") (pinfunction "1_1") (pintype "passive"))
      (node (ref "J8") (pin "16") (pinfunction "16_16") (pintype "passive"))
      (node (ref "U10") (pin "5") (pinfunction "5_5") (pintype "passive"))
    )
    (net (code "52") (name "/P15") (class "Default")
      (node (ref "J8") (pin "15") (pinfunction "15_15") (pintype "passive"))
      (node (ref "U10") (pin "6") (pinfunction "6_6") (pintype "passive"))
    )
    (net (code "53") (name "/P16") (class "Default")
      (node (ref "J8") (pin "14") (pinfunction "14_14") (pintype "passive"))
      (node (ref "U10") (pin "7") (pinfunction "7_7") (pintype "passive"))
    )
    (net (code "54") (name "/P17") (class "Default")
      (node (ref "J8") (pin "13") (pinfunction "13_13") (pintype "passive"))
      (node (ref "U10") (pin "8") (pinfunction "8_8") (pintype "passive"))
    )
    (net (code "55") (name "/P20") (class "Default")
      (node (ref "J5") (pin "11") (pinfunction "11_11") (pintype "passive"))
      (node (ref "J665") (pin "8") (pinfunction "8_8") (pintype "passive"))
      (node (ref "J9") (pin "20") (pinfunction "20_20") (pintype "passive"))
      (node (ref "U10") (pin "21") (pinfunction "21_21") (pintype "passive"))
    )
    (net (code "56") (name "/P21") (class "Default")
      (node (ref "J5") (pin "10") (pinfunction "10_10") (pintype "passive"))
      (node (ref "J665") (pin "7") (pinfunction "7_7") (pintype "passive"))
      (node (ref "J9") (pin "19") (pinfunction "19_19") (pintype "passive"))
      (node (ref "U10") (pin "22") (pinfunction "22_22") (pintype "passive"))
    )
    (net (code "57") (name "/P22") (class "Default")
      (node (ref "J5") (pin "9") (pinfunction "9_9") (pintype "passive"))
      (node (ref "J665") (pin "6") (pinfunction "6_6") (pintype "passive"))
      (node (ref "J9") (pin "18") (pinfunction "18_18") (pintype "passive"))
      (node (ref "U10") (pin "23") (pinfunction "23_23") (pintype "passive"))
    )
    (net (code "58") (name "/P23") (class "Default")
      (node (ref "J5") (pin "8") (pinfunction "8_8") (pintype "passive"))
      (node (ref "J665") (pin "5") (pinfunction "5_5") (pintype "passive"))
      (node (ref "J9") (pin "17") (pinfunction "17_17") (pintype "passive"))
      (node (ref "U10") (pin "24") (pinfunction "24_24") (pintype "passive"))
    )
    (net (code "59") (name "/P24") (class "Default")
      (node (ref "J5") (pin "7") (pinfunction "7_7") (pintype "passive"))
      (node (ref "J665") (pin "4") (pinfunction "4_4") (pintype "passive"))
      (node (ref "J9") (pin "16") (pinfunction "16_16") (pintype "passive"))
      (node (ref "U10") (pin "25") (pinfunction "25_25") (pintype "passive"))
    )
    (net (code "60") (name "/P25") (class "Default")
      (node (ref "J5") (pin "6") (pinfunction "6_6") (pintype "passive"))
      (node (ref "J665") (pin "3") (pinfunction "3_3") (pintype "passive"))
      (node (ref "J79") (pin "9") (pinfunction "9_9") (pintype "passive"))
      (node (ref "J9") (pin "15") (pinfunction "15_15") (pintype "passive"))
      (node (ref "U10") (pin "26") (pinfunction "26_26") (pintype "passive"))
    )
    (net (code "61") (name "/P26") (class "Default")
      (node (ref "J5") (pin "5") (pinfunction "5_5") (pintype "passive"))
      (node (ref "J665") (pin "2") (pinfunction "2_2") (pintype "passive"))
      (node (ref "J79") (pin "10") (pinfunction "10_10") (pintype "passive"))
      (node (ref "J9") (pin "14") (pinfunction "14_14") (pintype "passive"))
      (node (ref "U10") (pin "27") (pinfunction "27_27") (pintype "passive"))
    )
    (net (code "62") (name "/P27") (class "Default")
      (node (ref "J5") (pin "4") (pinfunction "4_4") (pintype "passive"))
      (node (ref "J665") (pin "1") (pinfunction "1_1") (pintype "passive"))
      (node (ref "J79") (pin "11") (pinfunction "11_11") (pintype "passive"))
      (node (ref "J9") (pin "13") (pinfunction "13_13") (pintype "passive"))
      (node (ref "U10") (pin "28") (pinfunction "28_28") (pintype "passive"))
    )
    (net (code "63") (name "/P30") (class "Default")
      (node (ref "J436") (pin "6") (pinfunction "6_6") (pintype "passive"))
      (node (ref "J8") (pin "11") (pinfunction "11_11") (pintype "passive"))
      (node (ref "U10") (pin "10") (pinfunction "10_10") (pintype "passive"))
    )
    (net (code "64") (name "/P31") (class "Default")
      (node (ref "J436") (pin "5") (pinfunction "5_5") (pintype "passive"))
      (node (ref "J8") (pin "10") (pinfunction "10_10") (pintype "passive"))
      (node (ref "U10") (pin "11") (pinfunction "11_11") (pintype "passive"))
    )
    (net (code "65") (name "/P32") (class "Default")
      (node (ref "J8") (pin "9") (pinfunction "9_9") (pintype "passive"))
      (node (ref "U10") (pin "12") (pinfunction "12_12") (pintype "passive"))
    )
    (net (code "66") (name "/P33") (class "Default")
      (node (ref "J8") (pin "8") (pinfunction "8_8") (pintype "passive"))
      (node (ref "J853") (pin "1") (pinfunction "1_1") (pintype "passive"))
      (node (ref "U10") (pin "13") (pinfunction "13_13") (pintype "passive"))
    )
    (net (code "67") (name "/P34") (class "Default")
      (node (ref "J8") (pin "7") (pinfunction "7_7") (pintype "passive"))
      (node (ref "U10") (pin "14") (pinfunction "14_14") (pintype "passive"))
    )
    (net (code "68") (name "/P35") (class "Default")
      (node (ref "J8") (pin "6") (pinfunction "6_6") (pintype "passive"))
      (node (ref "U10") (pin "15") (pinfunction "15_15") (pintype "passive"))
    )
    (net (code "69") (name "/P36") (class "Default")
      (node (ref "J8") (pin "5") (pinfunction "5_5") (pintype "passive"))
      (node (ref "U10") (pin "16") (pinfunction "16_16") (pintype "passive"))
    )
    (net (code "70") (name "/P37") (class "Default")
      (node (ref "J8") (pin "4") (pinfunction "4_4") (pintype "passive"))
      (node (ref "U10") (pin "17") (pinfunction "17_17") (pintype "passive"))
    )
    (net (code "71") (name "/PA0") (class "Default")
      (node (ref "S1") (pin "11") (pinfunction "A_11") (pintype "passive"))
      (node (ref "S2") (pin "11") (pinfunction "A_11") (pintype "passive"))
      (node (ref "U1") (pin "19") (pinfunction "1Q_19") (pintype "passive"))
    )
    (net (code "72") (name "/PA1") (class "Default")
      (node (ref "S1") (pin "7") (pinfunction "B_7") (pintype "passive"))
      (node (ref "S2") (pin "7") (pinfunction "B_7") (pintype "passive"))
      (node (ref "U1") (pin "18") (pinfunction "2Q_18") (pintype "passive"))
    )
    (net (code "73") (name "/PA2") (class "Default")
      (node (ref "S1") (pin "4") (pinfunction "C_4") (pintype "passive"))
      (node (ref "S2") (pin "4") (pinfunction "C_4") (pintype "passive"))
      (node (ref "U1") (pin "17") (pinfunction "3Q_17") (pintype "passive"))
    )
    (net (code "74") (name "/PA3") (class "Default")
      (node (ref "S1") (pin "2") (pinfunction "D_2") (pintype "passive"))
      (node (ref "S2") (pin "2") (pinfunction "D_2") (pintype "passive"))
      (node (ref "U1") (pin "16") (pinfunction "4Q_16") (pintype "passive"))
    )
    (net (code "75") (name "/PA4") (class "Default")
      (node (ref "S1") (pin "1") (pinfunction "E_1") (pintype "passive"))
      (node (ref "S2") (pin "1") (pinfunction "E_1") (pintype "passive"))
      (node (ref "U1") (pin "15") (pinfunction "5Q_15") (pintype "passive"))
    )
    (net (code "76") (name "/PA5") (class "Default")
      (node (ref "S1") (pin "10") (pinfunction "F_10") (pintype "passive"))
      (node (ref "S2") (pin "10") (pinfunction "F_10") (pintype "passive"))
      (node (ref "U1") (pin "14") (pinfunction "6Q_14") (pintype "passive"))
    )
    (net (code "77") (name "/PA6") (class "Default")
      (node (ref "S1") (pin "5") (pinfunction "G_5") (pintype "passive"))
      (node (ref "S2") (pin "5") (pinfunction "G_5") (pintype "passive"))
      (node (ref "U1") (pin "13") (pinfunction "7Q_13") (pintype "passive"))
    )
    (net (code "78") (name "/PA7") (class "Default")
      (node (ref "S1") (pin "3") (pinfunction "DP_3") (pintype "passive"))
      (node (ref "S2") (pin "3") (pinfunction "DP_3") (pintype "passive"))
      (node (ref "U1") (pin "12") (pinfunction "8Q_12") (pintype "passive"))
    )
    (net (code "79") (name "/PIN_3") (class "Default")
      (node (ref "U9") (pin "2") (pinfunction "3_2") (pintype "passive"))
    )
    (net (code "80") (name "/PIN_4") (class "Default")
      (node (ref "U9") (pin "16") (pinfunction "4_16") (pintype "passive"))
    )
    (net (code "81") (name "/PIN_7") (class "Default")
      (node (ref "U9") (pin "3") (pinfunction "7_3") (pintype "passive"))
    )
    (net (code "82") (name "/PIN_8") (class "Default")
      (node (ref "U9") (pin "17") (pinfunction "8_17") (pintype "passive"))
    )
    (net (code "83") (name "/PIN_9") (class "Default")
      (node (ref "U9") (pin "4") (pinfunction "9_4") (pintype "passive"))
    )
    (net (code "84") (name "/PIN_17") (class "Default")
      (node (ref "U9") (pin "6") (pinfunction "17_6") (pintype "passive"))
    )
    (net (code "85") (name "/PIN_18") (class "Default")
      (node (ref "U9") (pin "20") (pinfunction "18_20") (pintype "passive"))
    )
    (net (code "86") (name "/PIN_21") (class "Default")
      (node (ref "U9") (pin "21") (pinfunction "21_21") (pintype "passive"))
    )
    (net (code "87") (name "/PIN_22") (class "Default")
      (node (ref "U9") (pin "7") (pinfunction "22_7") (pintype "passive"))
    )
    (net (code "88") (name "/PIN_24") (class "Default")
      (node (ref "U9") (pin "22") (pinfunction "24_22") (pintype "passive"))
    )
    (net (code "89") (name "/PIN_25") (class "Default")
      (node (ref "U9") (pin "8") (pinfunction "25_8") (pintype "passive"))
    )
    (net (code "90") (name "/PIN_26") (class "Default")
      (node (ref "U9") (pin "23") (pinfunction "26_23") (pintype "passive"))
    )
    (net (code "91") (name "/PIN_27") (class "Default")
      (node (ref "U9") (pin "9") (pinfunction "27_9") (pintype "passive"))
    )
    (net (code "92") (name "/PIN_28") (class "Default")
      (node (ref "U9") (pin "25") (pinfunction "28_25") (pintype "passive"))
    )
    (net (code "93") (name "/PIN_30") (class "Default")
      (node (ref "U9") (pin "11") (pinfunction "30_11") (pintype "passive"))
    )
    (net (code "94") (name "/PIN_31") (class "Default")
      (node (ref "U9") (pin "26") (pinfunction "31_26") (pintype "passive"))
    )
    (net (code "95") (name "/PIN_32") (class "Default")
      (node (ref "U9") (pin "12") (pinfunction "32_12") (pintype "passive"))
    )
    (net (code "96") (name "/PIN_40") (class "Default")
      (node (ref "R2") (pin "2") (pinfunction "2_2") (pintype "passive"))
      (node (ref "U6") (pin "7") (pinfunction "DI0_7") (pintype "passive"))
      (node (ref "U9") (pin "29") (pinfunction "40_29") (pintype "passive"))
    )
    (net (code "97") (name "/PIN_41") (class "Default")
      (node (ref "RP6") (pin "2") (pinfunction "2_2") (pintype "passive"))
      (node (ref "U6") (pin "1") (pinfunction "CS/_1") (pintype "passive"))
      (node (ref "U9") (pin "43") (pinfunction "41_43") (pintype "passive"))
    )
    (net (code "98") (name "/PIN_42") (class "Default")
      (node (ref "R1") (pin "2") (pinfunction "2_2") (pintype "passive"))
      (node (ref "U6") (pin "6") (pinfunction "DI1_6") (pintype "passive"))
      (node (ref "U9") (pin "30") (pinfunction "42_30") (pintype "passive"))
    )
    (net (code "99") (name "/PIN_43") (class "Default")
      (node (ref "RP6") (pin "3") (pinfunction "3_3") (pintype "passive"))
      (node (ref "U6") (pin "2") (pinfunction "WR1_2") (pintype "passive"))
      (node (ref "U9") (pin "44") (pinfunction "43_44") (pintype "passive"))
    )
    (net (code "100") (name "/PIN_44") (class "Default")
      (node (ref "RP6") (pin "9") (pinfunction "9_9") (pintype "passive"))
      (node (ref "U6") (pin "5") (pinfunction "DI2_5") (pintype "passive"))
      (node (ref "U9") (pin "31") (pinfunction "44_31") (pintype "passive"))
    )
    (net (code "101") (name "/PIN_45") (class "Default")
      (node (ref "J3") (pin "11") (pinfunction "11_11") (pintype "passive"))
      (node (ref "U9") (pin "45") (pinfunction "45_45") (pintype "passive"))
    )
    (net (code "102") (name "/PIN_47") (class "Default")
      (node (ref "RP6") (pin "8") (pinfunction "8_8") (pintype "passive"))
      (node (ref "U6") (pin "4") (pinfunction "DI3_4") (pintype "passive"))
      (node (ref "U9") (pin "32") (pinfunction "47_32") (pintype "passive"))
    )
    (net (code "103") (name "/PIN_48") (class "Default")
      (node (ref "J3") (pin "10") (pinfunction "10_10") (pintype "passive"))
      (node (ref "U9") (pin "46") (pinfunction "48_46") (pintype "passive"))
    )
    (net (code "104") (name "/PIN_51") (class "Default")
      (node (ref "RP6") (pin "7") (pinfunction "7_7") (pintype "passive"))
      (node (ref "U6") (pin "16") (pinfunction "DI4_16") (pintype "passive"))
      (node (ref "U9") (pin "33") (pinfunction "51_33") (pintype "passive"))
    )
    (net (code "105") (name "/PIN_52") (class "Default")
      (node (ref "J3") (pin "9") (pinfunction "9_9") (pintype "passive"))
      (node (ref "U9") (pin "47") (pinfunction "52_47") (pintype "passive"))
    )
    (net (code "106") (name "/PIN_53") (class "Default")
      (node (ref "RP6") (pin "6") (pinfunction "6_6") (pintype "passive"))
      (node (ref "U6") (pin "15") (pinfunction "DI5_15") (pintype "passive"))
      (node (ref "U9") (pin "34") (pinfunction "53_34") (pintype "passive"))
    )
    (net (code "107") (name "/PIN_55") (class "Default")
      (node (ref "J3") (pin "8") (pinfunction "8_8") (pintype "passive"))
      (node (ref "U9") (pin "48") (pinfunction "55_48") (pintype "passive"))
    )
    (net (code "108") (name "/PIN_57") (class "Default")
      (node (ref "RP6") (pin "5") (pinfunction "5_5") (pintype "passive"))
      (node (ref "U6") (pin "14") (pinfunction "DI6_14") (pintype "passive"))
      (node (ref "U9") (pin "35") (pinfunction "57_35") (pintype "passive"))
    )
    (net (code "109") (name "/PIN_58") (class "Default")
      (node (ref "J3") (pin "7") (pinfunction "7_7") (pintype "passive"))
      (node (ref "U9") (pin "49") (pinfunction "58_49") (pintype "passive"))
    )
    (net (code "110") (name "/PIN_59") (class "Default")
      (node (ref "RP6") (pin "4") (pinfunction "4_4") (pintype "passive"))
      (node (ref "U6") (pin "13") (pinfunction "DI7_13") (pintype "passive"))
      (node (ref "U9") (pin "36") (pinfunction "59_36") (pintype "passive"))
    )
    (net (code "111") (name "/PIN_60") (class "Default")
      (node (ref "J3") (pin "6") (pinfunction "6_6") (pintype "passive"))
      (node (ref "U9") (pin "50") (pinfunction "60_50") (pintype "passive"))
    )
    (net (code "112") (name "/PIN_63") (class "Default")
      (node (ref "J853") (pin "3") (pinfunction "3_3") (pintype "passive"))
      (node (ref "U9") (pin "37") (pinfunction "63_37") (pintype "passive"))
    )
    (net (code "113") (name "/PIN_64") (class "Default")
      (node (ref "J3") (pin "5") (pinfunction "5_5") (pintype "passive"))
      (node (ref "U9") (pin "51") (pinfunction "64_51") (pintype "passive"))
    )
    (net (code "114") (name "/PIN_65") (class "Default")
      (node (ref "J675") (pin "8") (pinfunction "8_8") (pintype "passive"))
      (node (ref "U9") (pin "38") (pinfunction "65_38") (pintype "passive"))
    )
    (net (code "115") (name "/PIN_67") (class "Default")
      (node (ref "J3") (pin "4") (pinfunction "4_4") (pintype "passive"))
      (node (ref "U9") (pin "52") (pinfunction "67_52") (pintype "passive"))
    )
    (net (code "116") (name "/PIN_69") (class "Default")
      (node (ref "J675") (pin "7") (pinfunction "7_7") (pintype "passive"))
      (node (ref "U9") (pin "39") (pinfunction "69_39") (pintype "passive"))
    )
    (net (code "117") (name "/PIN_70") (class "Default")
      (node (ref "J436") (pin "2") (pinfunction "2_2") (pintype "passive"))
      (node (ref "J675") (pin "6") (pinfunction "6_6") (pintype "passive"))
      (node (ref "U9") (pin "53") (pinfunction "70_53") (pintype "passive"))
    )
    (net (code "118") (name "/PIN_71") (class "Default")
      (node (ref "J675") (pin "5") (pinfunction "5_5") (pintype "passive"))
      (node (ref "U9") (pin "40") (pinfunction "71_40") (pintype "passive"))
    )
    (net (code "119") (name "/PIN_72") (class "Default")
      (node (ref "J436") (pin "1") (pinfunction "1_1") (pintype "passive"))
      (node (ref "J675") (pin "4") (pinfunction "4_4") (pintype "passive"))
      (node (ref "U9") (pin "54") (pinfunction "72_54") (pintype "passive"))
    )
    (net (code "120") (name "/PIN_73") (class "Default")
      (node (ref "J675") (pin "3") (pinfunction "3_3") (pintype "passive"))
      (node (ref "U9") (pin "83") (pinfunction "73_83") (pintype "passive"))
    )
    (net (code "121") (name "/PIN_74") (class "Default")
      (node (ref "J675") (pin "2") (pinfunction "2_2") (pintype "passive"))
      (node (ref "U9") (pin "69") (pinfunction "74_69") (pintype "passive"))
    )
    (net (code "122") (name "/PIN_75") (class "Default")
      (node (ref "J675") (pin "1") (pinfunction "1_1") (pintype "passive"))
      (node (ref "U9") (pin "82") (pinfunction "75_82") (pintype "passive"))
    )
    (net (code "123") (name "/PIN_76") (class "Default")
      (node (ref "J301") (pin "3") (pinfunction "3_3") (pintype "passive"))
      (node (ref "U9") (pin "68") (pinfunction "76_68") (pintype "passive"))
    )
    (net (code "124") (name "/PIN_79") (class "Default")
      (node (ref "U9") (pin "81") (pinfunction "79_81") (pintype "passive"))
    )
    (net (code "125") (name "/PIN_80") (class "Default")
      (node (ref "J301") (pin "2") (pinfunction "2_2") (pintype "passive"))
      (node (ref "U9") (pin "67") (pinfunction "80_67") (pintype "passive"))
    )
    (net (code "126") (name "/PIN_81") (class "Default")
      (node (ref "J301") (pin "1") (pinfunction "1_1") (pintype "passive"))
      (node (ref "U9") (pin "80") (pinfunction "81_80") (pintype "passive"))
    )
    (net (code "127") (name "/PIN_86") (class "Default")
      (node (ref "U9") (pin "66") (pinfunction "86_66") (pintype "passive"))
    )
    (net (code "128") (name "/PIN_87") (class "Default")
      (node (ref "U9") (pin "79") (pinfunction "87_79") (pintype "passive"))
    )
    (net (code "129") (name "/PIN_88") (class "Default")
      (node (ref "U9") (pin "65") (pinfunction "88_65") (pintype "passive"))
    )
    (net (code "130") (name "/PIN_89") (class "Default")
      (node (ref "U9") (pin "78") (pinfunction "89_78") (pintype "passive"))
    )
    (net (code "131") (name "/PIN_90") (class "Default")
      (node (ref "U9") (pin "64") (pinfunction "90_64") (pintype "passive"))
    )
    (net (code "132") (name "/PIN_91") (class "Default")
      (node (ref "U9") (pin "77") (pinfunction "91_77") (pintype "passive"))
    )
    (net (code "133") (name "/PIN_92") (class "Default")
      (node (ref "J301") (pin "5") (pinfunction "5_5") (pintype "passive"))
      (node (ref "U9") (pin "63") (pinfunction "92_63") (pintype "passive"))
    )
    (net (code "134") (name "/PIN_93") (class "Default")
      (node (ref "U9") (pin "76") (pinfunction "93_76") (pintype "passive"))
    )
    (net (code "135") (name "/PIN_94") (class "Default")
      (node (ref "J301") (pin "4") (pinfunction "4_4") (pintype "passive"))
      (node (ref "U9") (pin "62") (pinfunction "94_62") (pintype "passive"))
    )
    (net (code "136") (name "/PIN_96") (class "Default")
      (node (ref "J3") (pin "1") (pinfunction "1_1") (pintype "passive"))
      (node (ref "U9") (pin "75") (pinfunction "96_75") (pintype "passive"))
    )
    (net (code "137") (name "/PIN_97") (class "Default")
      (node (ref "U9") (pin "61") (pinfunction "97_61") (pintype "passive"))
    )
    (net (code "138") (name "/PIN_99") (class "Default")
      (node (ref "J3") (pin "2") (pinfunction "2_2") (pintype "passive"))
      (node (ref "U9") (pin "74") (pinfunction "99_74") (pintype "passive"))
    )
    (net (code "139") (name "/PIN_100") (class "Default")
      (node (ref "U9") (pin "60") (pinfunction "100_60") (pintype "passive"))
    )
    (net (code "140") (name "/PIN_101") (class "Default")
      (node (ref "J3") (pin "3") (pinfunction "3_3") (pintype "passive"))
      (node (ref "U9") (pin "73") (pinfunction "101_73") (pintype "passive"))
    )
    (net (code "141") (name "/PIN_103") (class "Default")
      (node (ref "U9") (pin "59") (pinfunction "103_59") (pintype "passive"))
    )
    (net (code "142") (name "/PIN_104") (class "Default")
      (node (ref "J3") (pin "12") (pinfunction "12_12") (pintype "passive"))
      (node (ref "U9") (pin "72") (pinfunction "104_72") (pintype "passive"))
    )
    (net (code "143") (name "/PIN_112") (class "Default")
      (node (ref "J78") (pin "1") (pinfunction "1_1") (pintype "passive"))
      (node (ref "U9") (pin "111") (pinfunction "112_111") (pintype "passive"))
    )
    (net (code "144") (name "/PIN_113") (class "Default")
      (node (ref "J67") (pin "3") (pinfunction "3_3") (pintype "passive"))
      (node (ref "U9") (pin "97") (pinfunction "113_97") (pintype "passive"))
    )
    (net (code "145") (name "/PIN_114") (class "Default")
      (node (ref "J78") (pin "2") (pinfunction "2_2") (pintype "passive"))
      (node (ref "U9") (pin "110") (pinfunction "114_110") (pintype "passive"))
    )
    (net (code "146") (name "/PIN_115") (class "Default")
      (node (ref "J67") (pin "1") (pinfunction "1_1") (pintype "passive"))
      (node (ref "U9") (pin "96") (pinfunction "115_96") (pintype "passive"))
    )
    (net (code "147") (name "/PIN_118") (class "Default")
      (node (ref "J78") (pin "3") (pinfunction "3_3") (pintype "passive"))
      (node (ref "U9") (pin "109") (pinfunction "118_109") (pintype "passive"))
    )
    (net (code "148") (name "/PIN_119") (class "Default")
      (node (ref "J67") (pin "2") (pinfunction "2_2") (pintype "passive"))
      (node (ref "U9") (pin "95") (pinfunction "119_95") (pintype "passive"))
    )
    (net (code "149") (name "/PIN_120") (class "Default")
      (node (ref "J78") (pin "4") (pinfunction "4_4") (pintype "passive"))
      (node (ref "U9") (pin "108") (pinfunction "120_108") (pintype "passive"))
    )
    (net (code "150") (name "/PIN_121") (class "Default")
      (node (ref "J2") (pin "8") (pinfunction "8_8") (pintype "passive"))
      (node (ref "U9") (pin "94") (pinfunction "121_94") (pintype "passive"))
    )
    (net (code "151") (name "/PIN_122") (class "Default")
      (node (ref "J78") (pin "5") (pinfunction "5_5") (pintype "passive"))
      (node (ref "U9") (pin "107") (pinfunction "122_107") (pintype "passive"))
    )
    (net (code "152") (name "/PIN_125") (class "Default")
      (node (ref "J2") (pin "7") (pinfunction "7_7") (pintype "passive"))
      (node (ref "U9") (pin "93") (pinfunction "125_93") (pintype "passive"))
    )
    (net (code "153") (name "/PIN_126") (class "Default")
      (node (ref "J78") (pin "6") (pinfunction "6_6") (pintype "passive"))
      (node (ref "U9") (pin "106") (pinfunction "126_106") (pintype "passive"))
    )
    (net (code "154") (name "/PIN_129") (class "Default")
      (node (ref "J2") (pin "6") (pinfunction "6_6") (pintype "passive"))
      (node (ref "U9") (pin "92") (pinfunction "129_92") (pintype "passive"))
    )
    (net (code "155") (name "/PIN_132") (class "Default")
      (node (ref "J78") (pin "7") (pinfunction "7_7") (pintype "passive"))
      (node (ref "U9") (pin "105") (pinfunction "132_105") (pintype "passive"))
    )
    (net (code "156") (name "/PIN_133") (class "Default")
      (node (ref "J2") (pin "5") (pinfunction "5_5") (pintype "passive"))
      (node (ref "U9") (pin "91") (pinfunction "133_91") (pintype "passive"))
    )
    (net (code "157") (name "/PIN_134") (class "Default")
      (node (ref "J78") (pin "8") (pinfunction "8_8") (pintype "passive"))
      (node (ref "U9") (pin "104") (pinfunction "134_104") (pintype "passive"))
    )
    (net (code "158") (name "/PIN_135") (class "Default")
      (node (ref "J2") (pin "4") (pinfunction "4_4") (pintype "passive"))
      (node (ref "U9") (pin "90") (pinfunction "135_90") (pintype "passive"))
    )
    (net (code "159") (name "/PIN_136") (class "Default")
      (node (ref "J78") (pin "9") (pinfunction "9_9") (pintype "passive"))
      (node (ref "U9") (pin "103") (pinfunction "136_103") (pintype "passive"))
    )
    (net (code "160") (name "/PIN_137") (class "Default")
      (node (ref "J2") (pin "3") (pinfunction "3_3") (pintype "passive"))
      (node (ref "U9") (pin "89") (pinfunction "137_89") (pintype "passive"))
    )
    (net (code "161") (name "/PIN_139") (class "Default")
      (node (ref "J78") (pin "10") (pinfunction "10_10") (pintype "passive"))
      (node (ref "U9") (pin "102") (pinfunction "139_102") (pintype "passive"))
    )
    (net (code "162") (name "/PIN_141") (class "Default")
      (node (ref "J2") (pin "2") (pinfunction "2_2") (pintype "passive"))
      (node (ref "U9") (pin "88") (pinfunction "141_88") (pintype "passive"))
    )
    (net (code "163") (name "/PIN_142") (class "Default")
      (node (ref "J78") (pin "11") (pinfunction "11_11") (pintype "passive"))
      (node (ref "U9") (pin "101") (pinfunction "142_101") (pintype "passive"))
    )
    (net (code "164") (name "/PIN_143") (class "Default")
      (node (ref "J2") (pin "1") (pinfunction "1_1") (pintype "passive"))
      (node (ref "J579") (pin "2") (pinfunction "2_2") (pintype "passive"))
      (node (ref "R580") (pin "2") (pinfunction "2_2") (pintype "passive"))
      (node (ref "U9") (pin "87") (pinfunction "143_87") (pintype "passive"))
    )
    (net (code "165") (name "/RESET") (class "Default")
      (node (ref "J8") (pin "12") (pinfunction "12_12") (pintype "passive"))
      (node (ref "U10") (pin "9") (pinfunction "9_9") (pintype "passive"))
    )
    (net (code "166") (name "/SEG_1D") (class "Default")
      (node (ref "J4") (pin "11") (pinfunction "11_11") (pintype "passive"))
      (node (ref "U1") (pin "2") (pinfunction "1D_2") (pintype "passive"))
    )
    (net (code "167") (name "/SEG_2D") (class "Default")
      (node (ref "J4") (pin "10") (pinfunction "10_10") (pintype "passive"))
      (node (ref "U1") (pin "3") (pinfunction "2D_3") (pintype "passive"))
    )
    (net (code "168") (name "/SEG_3D") (class "Default")
      (node (ref "J4") (pin "9") (pinfunction "9_9") (pintype "passive"))
      (node (ref "U1") (pin "4") (pinfunction "3D_4") (pintype "passive"))
    )
    (net (code "169") (name "/SEG_4D") (class "Default")
      (node (ref "J4") (pin "8") (pinfunction "8_8") (pintype "passive"))
      (node (ref "U1") (pin "5") (pinfunction "4D_5") (pintype "passive"))
    )
    (net (code "170") (name "/SEG_5D") (class "Default")
      (node (ref "J4") (pin "7") (pinfunction "7_7") (pintype "passive"))
      (node (ref "U1") (pin "6") (pinfunction "5D_6") (pintype "passive"))
    )
    (net (code "171") (name "/SEG_6D") (class "Default")
      (node (ref "J4") (pin "6") (pinfunction "6_6") (pintype "passive"))
      (node (ref "U1") (pin "7") (pinfunction "6D_7") (pintype "passive"))
    )
    (net (code "172") (name "/SEG_7D") (class "Default")
      (node (ref "J4") (pin "5") (pinfunction "5_5") (pintype "passive"))
      (node (ref "U1") (pin "8") (pinfunction "7D_8") (pintype "passive"))
    )
    (net (code "173") (name "/SEG_8D") (class "Default")
      (node (ref "J4") (pin "4") (pinfunction "4_4") (pintype "passive"))
      (node (ref "U1") (pin "9") (pinfunction "8D_9") (pintype "passive"))
    )
    (net (code "174") (name "/SEG_C") (class "Default")
      (node (ref "J4") (pin "12") (pinfunction "12_12") (pintype "passive"))
      (node (ref "U1") (pin "11") (pinfunction "C_11") (pintype "passive"))
    )
    (net (code "175") (name "/TLC549_CLK") (class "Default")
      (node (ref "J68") (pin "3") (pinfunction "3_3") (pintype "passive"))
      (node (ref "U8") (pin "7") (pinfunction "I/O_CLK_7") (pintype "passive"))
    )
    (net (code "176") (name "/TLC549_CS") (class "Default")
      (node (ref "J68") (pin "2") (pinfunction "2_2") (pintype "passive"))
      (node (ref "U8") (pin "5") (pinfunction "CS_5") (pintype "passive"))
    )
    (net (code "177") (name "/TLC549_OUT") (class "Default")
      (node (ref "J68") (pin "1") (pinfunction "1_1") (pintype "passive"))
      (node (ref "U8") (pin "6") (pinfunction "D_OUT_6") (pintype "passive"))
    )
    (net (code "178") (name "/USART_RXD") (class "Default")
      (node (ref "J436") (pin "3") (pinfunction "3_3") (pintype "passive"))
      (node (ref "R1111") (pin "2") (pinfunction "2_2") (pintype "passive"))
      (node (ref "U7") (pin "5") (pinfunction "RXD_5") (pintype "passive"))
    )
    (net (code "179") (name "/USART_TXD") (class "Default")
      (node (ref "J436") (pin "4") (pinfunction "4_4") (pintype "passive"))
      (node (ref "R12") (pin "2") (pinfunction "2_2") (pintype "passive"))
      (node (ref "U7") (pin "1") (pinfunction "TXD_1") (pintype "passive"))
    )
    (net (code "180") (name "/VCC") (class "Default")
      (node (ref "J1000") (pin "1") (pinfunction "1_1") (pintype "passive"))
      (node (ref "U9") (pin "14") (pinfunction "VCC_14") (pintype "passive"))
      (node (ref "U9") (pin "28") (pinfunction "VCC_28") (pintype "passive"))
      (node (ref "U9") (pin "42") (pinfunction "VCC_42") (pintype "passive"))
      (node (ref "U9") (pin "56") (pinfunction "VCC_56") (pintype "passive"))
      (node (ref "U9") (pin "57") (pinfunction "VCC_57") (pintype "passive"))
      (node (ref "U9") (pin "85") (pinfunction "VCC_85") (pintype "passive"))
    )
    (net (code "181") (name "/VGA_B") (class "Default")
      (node (ref "J300") (pin "1") (pinfunction "1_1") (pintype "passive"))
      (node (ref "R300") (pin "2") (pinfunction "2_2") (pintype "passive"))
    )
    (net (code "182") (name "/VGA_G") (class "Default")
      (node (ref "J300") (pin "2") (pinfunction "2_2") (pintype "passive"))
      (node (ref "R301") (pin "2") (pinfunction "2_2") (pintype "passive"))
    )
    (net (code "183") (name "/VGA_HSY") (class "Default")
      (node (ref "COM1") (pin "13") (pinfunction "13_13") (pintype "passive"))
      (node (ref "J300") (pin "4") (pinfunction "4_4") (pintype "passive"))
    )
    (net (code "184") (name "/VGA_R") (class "Default")
      (node (ref "J300") (pin "3") (pinfunction "3_3") (pintype "passive"))
      (node (ref "R302") (pin "2") (pinfunction "2_2") (pintype "passive"))
    )
    (net (code "185") (name "/VGA_VSY") (class "Default")
      (node (ref "COM1") (pin "14") (pinfunction "14_14") (pintype "passive"))
      (node (ref "J300") (pin "5") (pinfunction "5_5") (pintype "passive"))
    )
    (net (code "186") (name "/X1") (class "Default")
      (node (ref "C12") (pin "1") (pinfunction "1_1") (pintype "passive"))
      (node (ref "J8") (pin "3") (pinfunction "3_3") (pintype "passive"))
      (node (ref "U10") (pin "18") (pinfunction "18_18") (pintype "passive"))
      (node (ref "Y2") (pin "1") (pinfunction "1_1") (pintype "passive"))
    )
    (net (code "187") (name "/X2") (class "Default")
      (node (ref "C11") (pin "1") (pinfunction "1_1") (pintype "passive"))
      (node (ref "J8") (pin "2") (pinfunction "2_2") (pintype "passive"))
      (node (ref "U10") (pin "19") (pinfunction "19_19") (pintype "passive"))
      (node (ref "Y2") (pin "2") (pinfunction "2_2") (pintype "passive"))
    )
    (net (code "188") (name "5VCC") (class "Default")
      (node (ref "C191") (pin "1") (pinfunction "1_1") (pintype "passive"))
      (node (ref "C6") (pin "1") (pinfunction "1_1") (pintype "passive"))
      (node (ref "F1") (pin "2") (pinfunction "2_2") (pintype "passive"))
      (node (ref "J222") (pin "15") (pinfunction "15_15") (pintype "passive"))
      (node (ref "J222") (pin "17") (pinfunction "17_17") (pintype "passive"))
      (node (ref "J222") (pin "19") (pinfunction "19_19") (pintype "passive"))
      (node (ref "J222") (pin "2") (pinfunction "2_2") (pintype "passive"))
      (node (ref "J435") (pin "1") (pinfunction "1_1") (pintype "passive"))
      (node (ref "J70") (pin "3") (pinfunction "3_3") (pintype "passive"))
      (node (ref "J9") (pin "1") (pinfunction "1_1") (pintype "passive"))
      (node (ref "R1") (pin "1") (pinfunction "1_1") (pintype "passive"))
      (node (ref "R13") (pin "1") (pinfunction "1_1") (pintype "passive"))
      (node (ref "R14") (pin "1") (pinfunction "1_1") (pintype "passive"))
      (node (ref "R18") (pin "1") (pinfunction "1_1") (pintype "passive"))
      (node (ref "R2") (pin "1") (pinfunction "1_1") (pintype "passive"))
      (node (ref "R2222") (pin "3") (pinfunction "3_3") (pintype "passive"))
      (node (ref "R3333") (pin "1") (pinfunction "1_1") (pintype "passive"))
      (node (ref "R552") (pin "1") (pinfunction "1_1") (pintype "passive"))
      (node (ref "R579") (pin "2") (pinfunction "2_2") (pintype "passive"))
      (node (ref "RP1") (pin "1") (pinfunction "1_1") (pintype "passive"))
      (node (ref "RP2") (pin "1") (pinfunction "1_1") (pintype "passive"))
      (node (ref "RP3") (pin "1") (pinfunction "1_1") (pintype "passive"))
      (node (ref "RP4") (pin "1") (pinfunction "1_1") (pintype "passive"))
      (node (ref "RP5") (pin "1") (pinfunction "1_1") (pintype "passive"))
      (node (ref "RP6") (pin "1") (pinfunction "1_1") (pintype "passive"))
      (node (ref "U1") (pin "20") (pinfunction "VCC_20") (pintype "passive"))
      (node (ref "U10") (pin "40") (pinfunction "40_40") (pintype "passive"))
      (node (ref "U222") (pin "15") (pinfunction "BLA_15") (pintype "passive"))
      (node (ref "U222") (pin "2") (pinfunction "VCC_2") (pintype "passive"))
      (node (ref "U3") (pin "16") (pinfunction "VCC_16") (pintype "passive"))
      (node (ref "U3") (pin "6") (pinfunction "E3_6") (pintype "passive"))
      (node (ref "U578") (pin "8") (pinfunction "8_8") (pintype "passive"))
      (node (ref "U6") (pin "19") (pinfunction "ILE_19") (pintype "passive"))
      (node (ref "U6") (pin "20") (pinfunction "VCC_20") (pintype "passive"))
      (node (ref "U6") (pin "8") (pinfunction "VREF_8") (pintype "passive"))
      (node (ref "U7") (pin "19") (pinfunction "RESET_19") (pintype "passive"))
      (node (ref "U7") (pin "20") (pinfunction "VDD_20") (pintype "passive"))
      (node (ref "U7") (pin "24") (pinfunction "VDD_PLL_24") (pintype "passive"))
      (node (ref "U7") (pin "8") (pinfunction "VDD_8") (pintype "passive"))
      (node (ref "U8") (pin "8") (pinfunction "VCC_8") (pintype "passive"))
      (node (ref "U9") (pin "5VCC") (pinfunction "5VCC_5VCC") (pintype "passive"))
    )
    (net (code "189") (name "GND") (class "Default")
      (node (ref "C10") (pin "2") (pinfunction "2_2") (pintype "passive"))
      (node (ref "C11") (pin "2") (pinfunction "2_2") (pintype "passive"))
      (node (ref "C12") (pin "2") (pinfunction "2_2") (pintype "passive"))
      (node (ref "C13") (pin "2") (pinfunction "2_2") (pintype "passive"))
      (node (ref "C191") (pin "2") (pinfunction "2_2") (pintype "passive"))
      (node (ref "C22") (pin "2") (pinfunction "2_2") (pintype "passive"))
      (node (ref "C26") (pin "2") (pinfunction "2_2") (pintype "passive"))
      (node (ref "C27") (pin "2") (pinfunction "2_2") (pintype "passive"))
      (node (ref "C6") (pin "2") (pinfunction "2_2") (pintype "passive"))
      (node (ref "C7") (pin "1") (pinfunction "1_1") (pintype "passive"))
      (node (ref "C8") (pin "2") (pinfunction "2_2") (pintype "passive"))
      (node (ref "C9") (pin "2") (pinfunction "2_2") (pintype "passive"))
      (node (ref "COM1") (pin "10") (pinfunction "10_10") (pintype "passive"))
      (node (ref "COM1") (pin "5") (pinfunction "5_5") (pintype "passive"))
      (node (ref "COM1") (pin "6") (pinfunction "6_6") (pintype "passive"))
      (node (ref "COM1") (pin "7") (pinfunction "7_7") (pintype "passive"))
      (node (ref "COM1") (pin "8") (pinfunction "8_8") (pintype "passive"))
      (node (ref "D12") (pin "1") (pinfunction "1_1") (pintype "passive"))
      (node (ref "D552") (pin "2") (pinfunction "2_2") (pintype "passive"))
      (node (ref "DC1") (pin "2") (pinfunction "GND_2") (pintype "passive"))
      (node (ref "DC1") (pin "3") (pinfunction "GND_3") (pintype "passive"))
      (node (ref "J10") (pin "2") (pinfunction "2_2") (pintype "passive"))
      (node (ref "J222") (pin "1") (pinfunction "1_1") (pintype "passive"))
      (node (ref "J222") (pin "20") (pinfunction "20_20") (pintype "passive"))
      (node (ref "J6") (pin "3") (pinfunction "3_3") (pintype "passive"))
      (node (ref "J66") (pin "1") (pinfunction "1_1") (pintype "passive"))
      (node (ref "J7") (pin "2") (pinfunction "2_2") (pintype "passive"))
      (node (ref "J8") (pin "1") (pinfunction "1_1") (pintype "passive"))
      (node (ref "Q1") (pin "3") (pinfunction "Collector_3") (pintype "passive"))
      (node (ref "R21") (pin "1") (pinfunction "1_1") (pintype "passive"))
      (node (ref "R2222") (pin "1") (pinfunction "1_1") (pintype "passive"))
      (node (ref "R25") (pin "1") (pinfunction "1_1") (pintype "passive"))
      (node (ref "R3333") (pin "3") (pinfunction "3_3") (pintype "passive"))
      (node (ref "R580") (pin "1") (pinfunction "1_1") (pintype "passive"))
      (node (ref "S3") (pin "1") (pinfunction "1_1") (pintype "passive"))
      (node (ref "S3") (pin "2") (pinfunction "2_2") (pintype "passive"))
      (node (ref "S3") (pin "3") (pinfunction "3_3") (pintype "passive"))
      (node (ref "S3") (pin "4") (pinfunction "4_4") (pintype "passive"))
      (node (ref "S4") (pin "1") (pinfunction "1_1") (pintype "passive"))
      (node (ref "S4") (pin "2") (pinfunction "2_2") (pintype "passive"))
      (node (ref "S4") (pin "3") (pinfunction "3_3") (pintype "passive"))
      (node (ref "S4") (pin "4") (pinfunction "4_4") (pintype "passive"))
      (node (ref "U1") (pin "1") (pinfunction "~{OC}_1") (pintype "passive"))
      (node (ref "U1") (pin "10") (pinfunction "GND_10") (pintype "passive"))
      (node (ref "U10") (pin "20") (pinfunction "20_20") (pintype "passive"))
      (node (ref "U18") (pin "2") (pinfunction "GND_2") (pintype "passive"))
      (node (ref "U222") (pin "1") (pinfunction "VSS_1") (pintype "passive"))
      (node (ref "U222") (pin "16") (pinfunction "BLK_16") (pintype "passive"))
      (node (ref "U3") (pin "4") (pinfunction "~{E1}_4") (pintype "passive"))
      (node (ref "U3") (pin "5") (pinfunction "~{E2}_5") (pintype "passive"))
      (node (ref "U3") (pin "8") (pinfunction "GND_8") (pintype "passive"))
      (node (ref "U4") (pin "3") (pinfunction "+_3") (pintype "passive"))
      (node (ref "U578") (pin "2") (pinfunction "-_2") (pintype "passive"))
      (node (ref "U6") (pin "10") (pinfunction "GND_10") (pintype "passive"))
      (node (ref "U6") (pin "12") (pinfunction "IOUT2_12") (pintype "passive"))
      (node (ref "U6") (pin "17") (pinfunction "XFER_17") (pintype "passive"))
      (node (ref "U6") (pin "18") (pinfunction "WR2_18") (pintype "passive"))
      (node (ref "U6") (pin "3") (pinfunction "GND_3") (pintype "passive"))
      (node (ref "U7") (pin "18") (pinfunction "GND_3.3_18") (pintype "passive"))
      (node (ref "U7") (pin "21") (pinfunction "GND_21") (pintype "passive"))
      (node (ref "U7") (pin "25") (pinfunction "GND_PLL_25") (pintype "passive"))
      (node (ref "U7") (pin "26") (pinfunction "PLL_TEST_26") (pintype "passive"))
      (node (ref "U7") (pin "7") (pinfunction "GND_7") (pintype "passive"))
      (node (ref "U8") (pin "3") (pinfunction "REF-_3") (pintype "passive"))
      (node (ref "U8") (pin "4") (pinfunction "GND_4") (pintype "passive"))
      (node (ref "U9") (pin "1") (pinfunction "GND_1") (pintype "passive"))
      (node (ref "U9") (pin "100") (pinfunction "GND_100") (pintype "passive"))
      (node (ref "U9") (pin "112") (pinfunction "GND_112") (pintype "passive"))
      (node (ref "U9") (pin "13") (pinfunction "GND_13") (pintype "passive"))
      (node (ref "U9") (pin "15") (pinfunction "GND_15") (pintype "passive"))
      (node (ref "U9") (pin "18") (pinfunction "GND_18") (pintype "passive"))
      (node (ref "U9") (pin "19") (pinfunction "GND_19") (pintype "passive"))
      (node (ref "U9") (pin "27") (pinfunction "GND_27") (pintype "passive"))
      (node (ref "U9") (pin "41") (pinfunction "GND_41") (pintype "passive"))
      (node (ref "U9") (pin "5") (pinfunction "GND_5") (pintype "passive"))
      (node (ref "U9") (pin "55") (pinfunction "GND_55") (pintype "passive"))
      (node (ref "U9") (pin "58") (pinfunction "GND_58") (pintype "passive"))
      (node (ref "U9") (pin "70") (pinfunction "GND_70") (pintype "passive"))
      (node (ref "U9") (pin "71") (pinfunction "GND_71") (pintype "passive"))
      (node (ref "U9") (pin "84") (pinfunction "GND_84") (pintype "passive"))
      (node (ref "U9") (pin "86") (pinfunction "GND_86") (pintype "passive"))
      (node (ref "U9") (pin "98") (pinfunction "GND_98") (pintype "passive"))
      (node (ref "U9") (pin "99") (pinfunction "GND_99") (pintype "passive"))
      (node (ref "U9") (pin "GND") (pinfunction "GND_GND") (pintype "passive"))
      (node (ref "USB1") (pin "4") (pinfunction "GND_4") (pintype "passive"))
    )
    (net (code "190") (name "Net-(C111-Pad1)") (class "Default")
      (node (ref "C111") (pin "1") (pinfunction "1_1") (pintype "passive"))
      (node (ref "C121") (pin "2") (pinfunction "2_2") (pintype "passive"))
      (node (ref "R9") (pin "1") (pinfunction "1_1") (pintype "passive"))
      (node (ref "U4") (pin "7") (pinfunction "7_7") (pintype "passive"))
    )
    (net (code "191") (name "Net-(C111-Pad2)") (class "Default")
      (node (ref "C111") (pin "2") (pinfunction "2_2") (pintype "passive"))
      (node (ref "J10") (pin "1") (pinfunction "1_1") (pintype "passive"))
    )
    (net (code "192") (name "Net-(COM1-Pad1)") (class "Default")
      (node (ref "COM1") (pin "1") (pinfunction "1_1") (pintype "passive"))
      (node (ref "R302") (pin "1") (pinfunction "1_1") (pintype "passive"))
    )
    (net (code "193") (name "Net-(COM1-Pad2)") (class "Default")
      (node (ref "COM1") (pin "2") (pinfunction "2_2") (pintype "passive"))
      (node (ref "R301") (pin "1") (pinfunction "1_1") (pintype "passive"))
    )
    (net (code "194") (name "Net-(COM1-Pad3)") (class "Default")
      (node (ref "COM1") (pin "3") (pinfunction "3_3") (pintype "passive"))
      (node (ref "R300") (pin "1") (pinfunction "1_1") (pintype "passive"))
    )
    (net (code "195") (name "Net-(D1-Pad2)") (class "Default")
      (node (ref "D1") (pin "2") (pinfunction "2_2") (pintype "passive"))
      (node (ref "R1111") (pin "1") (pinfunction "1_1") (pintype "passive"))
    )
    (net (code "196") (name "Net-(D2-Pad2)") (class "Default")
      (node (ref "D2") (pin "2") (pinfunction "2_2") (pintype "passive"))
      (node (ref "R12") (pin "1") (pinfunction "1_1") (pintype "passive"))
    )
    (net (code "197") (name "Net-(D100-Pad1)") (class "Default")
      (node (ref "D100") (pin "1") (pinfunction "1_1") (pintype "passive"))
      (node (ref "RP4") (pin "2") (pinfunction "2_2") (pintype "passive"))
    )
    (net (code "198") (name "Net-(D101-Pad1)") (class "Default")
      (node (ref "D101") (pin "1") (pinfunction "1_1") (pintype "passive"))
      (node (ref "RP4") (pin "3") (pinfunction "3_3") (pintype "passive"))
    )
    (net (code "199") (name "Net-(D102-Pad1)") (class "Default")
      (node (ref "D102") (pin "1") (pinfunction "1_1") (pintype "passive"))
      (node (ref "RP4") (pin "4") (pinfunction "4_4") (pintype "passive"))
    )
    (net (code "200") (name "Net-(D103-Pad1)") (class "Default")
      (node (ref "D103") (pin "1") (pinfunction "1_1") (pintype "passive"))
      (node (ref "RP4") (pin "5") (pinfunction "5_5") (pintype "passive"))
    )
    (net (code "201") (name "Net-(D104-Pad1)") (class "Default")
      (node (ref "D104") (pin "1") (pinfunction "1_1") (pintype "passive"))
      (node (ref "RP4") (pin "6") (pinfunction "6_6") (pintype "passive"))
    )
    (net (code "202") (name "Net-(D105-Pad1)") (class "Default")
      (node (ref "D105") (pin "1") (pinfunction "1_1") (pintype "passive"))
      (node (ref "RP4") (pin "7") (pinfunction "7_7") (pintype "passive"))
    )
    (net (code "203") (name "Net-(D106-Pad1)") (class "Default")
      (node (ref "D106") (pin "1") (pinfunction "1_1") (pintype "passive"))
      (node (ref "RP4") (pin "8") (pinfunction "8_8") (pintype "passive"))
    )
    (net (code "204") (name "Net-(D107-Pad1)") (class "Default")
      (node (ref "D107") (pin "1") (pinfunction "1_1") (pintype "passive"))
      (node (ref "RP4") (pin "9") (pinfunction "9_9") (pintype "passive"))
    )
    (net (code "205") (name "Net-(D552-Pad1)") (class "Default")
      (node (ref "D552") (pin "1") (pinfunction "1_1") (pintype "passive"))
      (node (ref "R552") (pin "2") (pinfunction "2_2") (pintype "passive"))
    )
    (net (code "206") (name "Net-(D578-Pad1)") (class "Default")
      (node (ref "D578") (pin "1") (pinfunction "1_1") (pintype "passive"))
      (node (ref "J579") (pin "1") (pinfunction "1_1") (pintype "passive"))
      (node (ref "R579") (pin "1") (pinfunction "1_1") (pintype "passive"))
      (node (ref "U578") (pin "1") (pinfunction "1_1") (pintype "passive"))
    )
    (net (code "207") (name "Net-(D578-Pad2)") (class "Default")
      (node (ref "D578") (pin "2") (pinfunction "2_2") (pintype "passive"))
      (node (ref "D579") (pin "2") (pinfunction "2_2") (pintype "passive"))
    )
    (net (code "208") (name "Net-(D579-Pad1)") (class "Default")
      (node (ref "D579") (pin "1") (pinfunction "1_1") (pintype "passive"))
      (node (ref "U578") (pin "4") (pinfunction "4_4") (pintype "passive"))
    )
    (net (code "209") (name "Net-(DC1-VCC)") (class "Default")
      (node (ref "D14") (pin "1") (pinfunction "1_1") (pintype "passive"))
      (node (ref "DC1") (pin "1") (pinfunction "VCC_1") (pintype "passive"))
    )
    (net (code "210") (name "Net-(F1-Pad1)") (class "Default")
      (node (ref "F1") (pin "1") (pinfunction "1_1") (pintype "passive"))
      (node (ref "SW1") (pin "3") (pinfunction "3_3") (pintype "passive"))
    )
    (net (code "211") (name "Net-(J6-Pad2)") (class "Default")
      (node (ref "J6") (pin "2") (pinfunction "2_2") (pintype "passive"))
      (node (ref "S18") (pin "1") (pinfunction "1_1") (pintype "passive"))
      (node (ref "S19") (pin "1") (pinfunction "1_1") (pintype "passive"))
      (node (ref "S20") (pin "1") (pinfunction "1_1") (pintype "passive"))
      (node (ref "S8") (pin "1") (pinfunction "1_1") (pintype "passive"))
    )
    (net (code "212") (name "Net-(J9-Pad11)") (class "Default")
      (node (ref "J9") (pin "11") (pinfunction "11_11") (pintype "passive"))
      (node (ref "U10") (pin "30") (pinfunction "30_30") (pintype "passive"))
    )
    (net (code "213") (name "Net-(J9-Pad12)") (class "Default")
      (node (ref "J9") (pin "12") (pinfunction "12_12") (pintype "passive"))
      (node (ref "U10") (pin "29") (pinfunction "29_29") (pintype "passive"))
    )
    (net (code "214") (name "Net-(J222-Pad3)") (class "Default")
      (node (ref "J222") (pin "3") (pinfunction "3_3") (pintype "passive"))
      (node (ref "R3333") (pin "2") (pinfunction "2_2") (pintype "passive"))
    )
    (net (code "215") (name "Net-(J578-Pad1)") (class "Default")
      (node (ref "J578") (pin "1") (pinfunction "1_1") (pintype "passive"))
      (node (ref "J578") (pin "2") (pinfunction "2_2") (pintype "passive"))
      (node (ref "R578") (pin "1") (pinfunction "1_1") (pintype "passive"))
    )
    (net (code "216") (name "Net-(Q1-Base)") (class "Default")
      (node (ref "Q1") (pin "1") (pinfunction "Base_1") (pintype "passive"))
      (node (ref "R4") (pin "2") (pinfunction "2_2") (pintype "passive"))
    )
    (net (code "217") (name "Net-(Q1-Emitter)") (class "Default")
      (node (ref "Q1") (pin "2") (pinfunction "Emitter_2") (pintype "passive"))
      (node (ref "U5") (pin "2") (pinfunction "2_2") (pintype "passive"))
    )
    (net (code "218") (name "Net-(R5-Pad1)") (class "Default")
      (node (ref "R5") (pin "1") (pinfunction "1_1") (pintype "passive"))
      (node (ref "U5") (pin "1") (pinfunction "1_1") (pintype "passive"))
    )
    (net (code "219") (name "Net-(S1-LED1)") (class "Default")
      (node (ref "S1") (pin "6") (pinfunction "LED1_6") (pintype "passive"))
      (node (ref "U3") (pin "12") (pinfunction "Y3_12") (pintype "passive"))
    )
    (net (code "220") (name "Net-(S1-LED2)") (class "Default")
      (node (ref "S1") (pin "8") (pinfunction "LED2_8") (pintype "passive"))
      (node (ref "U3") (pin "13") (pinfunction "Y2_13") (pintype "passive"))
    )
    (net (code "221") (name "Net-(S1-LED3)") (class "Default")
      (node (ref "S1") (pin "9") (pinfunction "LED3_9") (pintype "passive"))
      (node (ref "U3") (pin "14") (pinfunction "Y1_14") (pintype "passive"))
    )
    (net (code "222") (name "Net-(S1-LED4)") (class "Default")
      (node (ref "S1") (pin "12") (pinfunction "LED4_12") (pintype "passive"))
      (node (ref "U3") (pin "15") (pinfunction "Y0_15") (pintype "passive"))
    )
    (net (code "223") (name "Net-(S2-LED1)") (class "Default")
      (node (ref "S2") (pin "6") (pinfunction "LED1_6") (pintype "passive"))
      (node (ref "U3") (pin "7") (pinfunction "Y7_7") (pintype "passive"))
    )
    (net (code "224") (name "Net-(S2-LED2)") (class "Default")
      (node (ref "S2") (pin "8") (pinfunction "LED2_8") (pintype "passive"))
      (node (ref "U3") (pin "9") (pinfunction "Y6_9") (pintype "passive"))
    )
    (net (code "225") (name "Net-(S2-LED3)") (class "Default")
      (node (ref "S2") (pin "9") (pinfunction "LED3_9") (pintype "passive"))
      (node (ref "U3") (pin "10") (pinfunction "Y5_10") (pintype "passive"))
    )
    (net (code "226") (name "Net-(S2-LED4)") (class "Default")
      (node (ref "S2") (pin "12") (pinfunction "LED4_12") (pintype "passive"))
      (node (ref "U3") (pin "11") (pinfunction "Y4_11") (pintype "passive"))
    )
    (net (code "227") (name "Net-(U4A--)") (class "Default")
      (node (ref "U4") (pin "2") (pinfunction "-_2") (pintype "passive"))
      (node (ref "U6") (pin "11") (pinfunction "IOUT1_11") (pintype "passive"))
    )
    (net (code "228") (name "Net-(U4B-+)") (class "Default")
      (node (ref "R21") (pin "2") (pinfunction "2_2") (pintype "passive"))
      (node (ref "U4") (pin "5") (pinfunction "+_5") (pintype "passive"))
    )
    (net (code "229") (name "Net-(U4B--)") (class "Default")
      (node (ref "C121") (pin "1") (pinfunction "1_1") (pintype "passive"))
      (node (ref "R8") (pin "1") (pinfunction "1_1") (pintype "passive"))
      (node (ref "R9") (pin "2") (pinfunction "2_2") (pintype "passive"))
      (node (ref "U4") (pin "6") (pinfunction "-_6") (pintype "passive"))
    )
    (net (code "230") (name "Net-(U6-RFB)") (class "Default")
      (node (ref "R8") (pin "2") (pinfunction "2_2") (pintype "passive"))
      (node (ref "U4") (pin "1") (pintype "passive"))
      (node (ref "U6") (pin "9") (pinfunction "RFB_9") (pintype "passive"))
    )
    (net (code "231") (name "Net-(U7-DM)") (class "Default")
      (node (ref "R15") (pin "2") (pinfunction "2_2") (pintype "passive"))
      (node (ref "U7") (pin "16") (pinfunction "DM_16") (pintype "passive"))
    )
    (net (code "232") (name "Net-(U7-DP)") (class "Default")
      (node (ref "R17") (pin "2") (pinfunction "2_2") (pintype "passive"))
      (node (ref "U7") (pin "15") (pinfunction "DP_15") (pintype "passive"))
    )
    (net (code "233") (name "Net-(U7-LD_MODE)") (class "Default")
      (node (ref "R13") (pin "2") (pinfunction "2_2") (pintype "passive"))
      (node (ref "U7") (pin "23") (pinfunction "LD_MODE_23") (pintype "passive"))
    )
    (net (code "234") (name "Net-(U7-OSC1)") (class "Default")
      (node (ref "C9") (pin "1") (pinfunction "1_1") (pintype "passive"))
      (node (ref "U7") (pin "27") (pinfunction "OSC1_27") (pintype "passive"))
      (node (ref "Y1") (pin "2") (pinfunction "2_2") (pintype "passive"))
    )
    (net (code "235") (name "Net-(U7-OSC2)") (class "Default")
      (node (ref "C8") (pin "1") (pinfunction "1_1") (pintype "passive"))
      (node (ref "U7") (pin "28") (pinfunction "OSC2_28") (pintype "passive"))
      (node (ref "Y1") (pin "1") (pinfunction "1_1") (pintype "passive"))
    )
    (net (code "236") (name "Net-(U7-TRI_STATE)") (class "Default")
      (node (ref "R14") (pin "2") (pinfunction "2_2") (pintype "passive"))
      (node (ref "U7") (pin "22") (pinfunction "TRI_STATE_22") (pintype "passive"))
    )
    (net (code "237") (name "Net-(U18-BST)") (class "Default")
      (node (ref "C21") (pin "1") (pinfunction "1_1") (pintype "passive"))
      (node (ref "U18") (pin "1") (pinfunction "BST_1") (pintype "passive"))
    )
    (net (code "238") (name "Net-(U18-EN)") (class "Default")
      (node (ref "R26") (pin "2") (pinfunction "2_2") (pintype "passive"))
      (node (ref "U18") (pin "4") (pinfunction "EN_4") (pintype "passive"))
    )
    (net (code "239") (name "Net-(U18-FB)") (class "Default")
      (node (ref "R25") (pin "2") (pinfunction "2_2") (pintype "passive"))
      (node (ref "R29") (pin "1") (pinfunction "1_1") (pintype "passive"))
      (node (ref "U18") (pin "3") (pinfunction "FB_3") (pintype "passive"))
    )
    (net (code "240") (name "Net-(U18-IN)") (class "Default")
      (node (ref "C26") (pin "1") (pinfunction "1_1") (pintype "passive"))
      (node (ref "C27") (pin "1") (pinfunction "1_1") (pintype "passive"))
      (node (ref "D14") (pin "2") (pinfunction "2_2") (pintype "passive"))
      (node (ref "R26") (pin "1") (pinfunction "1_1") (pintype "passive"))
      (node (ref "U18") (pin "5") (pinfunction "IN_5") (pintype "passive"))
    )
    (net (code "241") (name "Net-(U18-SW)") (class "Default")
      (node (ref "C21") (pin "2") (pinfunction "2_2") (pintype "passive"))
      (node (ref "D12") (pin "2") (pinfunction "2_2") (pintype "passive"))
      (node (ref "L1") (pin "1") (pinfunction "1_1") (pintype "passive"))
      (node (ref "U18") (pin "6") (pinfunction "SW_6") (pintype "passive"))
    )
    (net (code "242") (name "Net-(U222-V0)") (class "Default")
      (node (ref "R2222") (pin "2") (pinfunction "2_2") (pintype "passive"))
      (node (ref "U222") (pin "3") (pinfunction "V0_3") (pintype "passive"))
    )
    (net (code "243") (name "Net-(U578A-+)") (class "Default")
      (node (ref "R578") (pin "2") (pinfunction "2_2") (pintype "passive"))
      (node (ref "U578") (pin "3") (pinfunction "+_3") (pintype "passive"))
    )
    (net (code "244") (name "Net-(USB1-D+)") (class "Default")
      (node (ref "R15") (pin "1") (pinfunction "1_1") (pintype "passive"))
      (node (ref "R16") (pin "1") (pinfunction "1_1") (pintype "passive"))
      (node (ref "USB1") (pin "3") (pinfunction "D+_3") (pintype "passive"))
    )
    (net (code "245") (name "Net-(USB1-D-)") (class "Default")
      (node (ref "R17") (pin "1") (pinfunction "1_1") (pintype "passive"))
      (node (ref "USB1") (pin "2") (pinfunction "D-_2") (pintype "passive"))
    )
    (net (code "246") (name "PL2303_VCC") (class "Default")
      (node (ref "C10") (pin "1") (pinfunction "1_1") (pintype "passive"))
      (node (ref "D1") (pin "1") (pinfunction "1_1") (pintype "passive"))
      (node (ref "D2") (pin "1") (pinfunction "1_1") (pintype "passive"))
      (node (ref "J435") (pin "2") (pinfunction "2_2") (pintype "passive"))
      (node (ref "U7") (pin "4") (pinfunction "VDD_325_4") (pintype "passive"))
    )
    (net (code "247") (name "VUSB") (class "Default")
      (node (ref "C13") (pin "1") (pinfunction "1_1") (pintype "passive"))
      (node (ref "C22") (pin "1") (pinfunction "1_1") (pintype "passive"))
      (node (ref "L1") (pin "2") (pinfunction "2_2") (pintype "passive"))
      (node (ref "R29") (pin "2") (pinfunction "2_2") (pintype "passive"))
      (node (ref "SW1") (pin "2") (pinfunction "2_2") (pintype "passive"))
      (node (ref "USB1") (pin "1") (pinfunction "VBUS_1") (pintype "passive"))
    )
    (net (code "248") (name "unconnected-(COM1-Pad4)") (class "Default")
      (node (ref "COM1") (pin "4") (pinfunction "4_4") (pintype "passive+no_connect"))
    )
    (net (code "249") (name "unconnected-(COM1-Pad9)") (class "Default")
      (node (ref "COM1") (pin "9") (pinfunction "9_9") (pintype "passive+no_connect"))
    )
    (net (code "250") (name "unconnected-(COM1-Pad11)") (class "Default")
      (node (ref "COM1") (pin "11") (pinfunction "11_11") (pintype "passive+no_connect"))
    )
    (net (code "251") (name "unconnected-(COM1-Pad12)") (class "Default")
      (node (ref "COM1") (pin "12") (pinfunction "12_12") (pintype "passive+no_connect"))
    )
    (net (code "252") (name "unconnected-(COM1-Pad15)") (class "Default")
      (node (ref "COM1") (pin "15") (pinfunction "15_15") (pintype "passive+no_connect"))
    )
    (net (code "253") (name "unconnected-(COM1-Pad16)") (class "Default")
      (node (ref "COM1") (pin "16") (pinfunction "16_16") (pintype "passive+no_connect"))
    )
    (net (code "254") (name "unconnected-(COM1-Pad17)") (class "Default")
      (node (ref "COM1") (pin "17") (pinfunction "17_17") (pintype "passive+no_connect"))
    )
    (net (code "255") (name "unconnected-(J222-Pad16)") (class "Default")
      (node (ref "J222") (pin "16") (pinfunction "16_16") (pintype "passive"))
    )
    (net (code "256") (name "unconnected-(J222-Pad18)") (class "Default")
      (node (ref "J222") (pin "18") (pinfunction "18_18") (pintype "passive"))
    )
    (net (code "257") (name "unconnected-(SW1-Pad1)") (class "Default")
      (node (ref "SW1") (pin "1") (pinfunction "1_1") (pintype "passive+no_connect"))
    )
    (net (code "258") (name "unconnected-(U7-CTS_N-Pad11)") (class "Default")
      (node (ref "U7") (pin "11") (pinfunction "CTS_N_11") (pintype "passive+no_connect"))
    )
    (net (code "259") (name "unconnected-(U7-DCD_N-Pad10)") (class "Default")
      (node (ref "U7") (pin "10") (pinfunction "DCD_N_10") (pintype "passive+no_connect"))
    )
    (net (code "260") (name "unconnected-(U7-DSR_N-Pad9)") (class "Default")
      (node (ref "U7") (pin "9") (pinfunction "DSR_N_9") (pintype "passive+no_connect"))
    )
    (net (code "261") (name "unconnected-(U7-DTR_N-Pad2)") (class "Default")
      (node (ref "U7") (pin "2") (pinfunction "DTR_N_2") (pintype "passive"))
    )
    (net (code "262") (name "unconnected-(U7-EE_CLK-Pad13)") (class "Default")
      (node (ref "U7") (pin "13") (pinfunction "EE_CLK_13") (pintype "passive+no_connect"))
    )
    (net (code "263") (name "unconnected-(U7-EE_DATA-Pad14)") (class "Default")
      (node (ref "U7") (pin "14") (pinfunction "EE_DATA_14") (pintype "passive+no_connect"))
    )
    (net (code "264") (name "unconnected-(U7-RL_N-Pad6)") (class "Default")
      (node (ref "U7") (pin "6") (pinfunction "RL_N_6") (pintype "passive+no_connect"))
    )
    (net (code "265") (name "unconnected-(U7-RTS_N-Pad3)") (class "Default")
      (node (ref "U7") (pin "3") (pinfunction "RTS_N_3") (pintype "passive"))
    )
    (net (code "266") (name "unconnected-(U7-SHTD_N-Pad12)") (class "Default")
      (node (ref "U7") (pin "12") (pinfunction "SHTD_N_12") (pintype "passive+no_connect"))
    )
    (net (code "267") (name "unconnected-(USB1-shell-Pad5)") (class "Default")
      (node (ref "USB1") (pin "5") (pinfunction "shell_5") (pintype "passive+no_connect"))
    )
    (net (code "268") (name "unconnected-(USB1-shell-Pad6)") (class "Default")
      (node (ref "USB1") (pin "6") (pinfunction "shell_6") (pintype "passive+no_connect"))
    )
  )
)
